# AT_SoM_Carrier_Board_V1_1.net
KiCad netlist of a schematic drawn in EAGLE
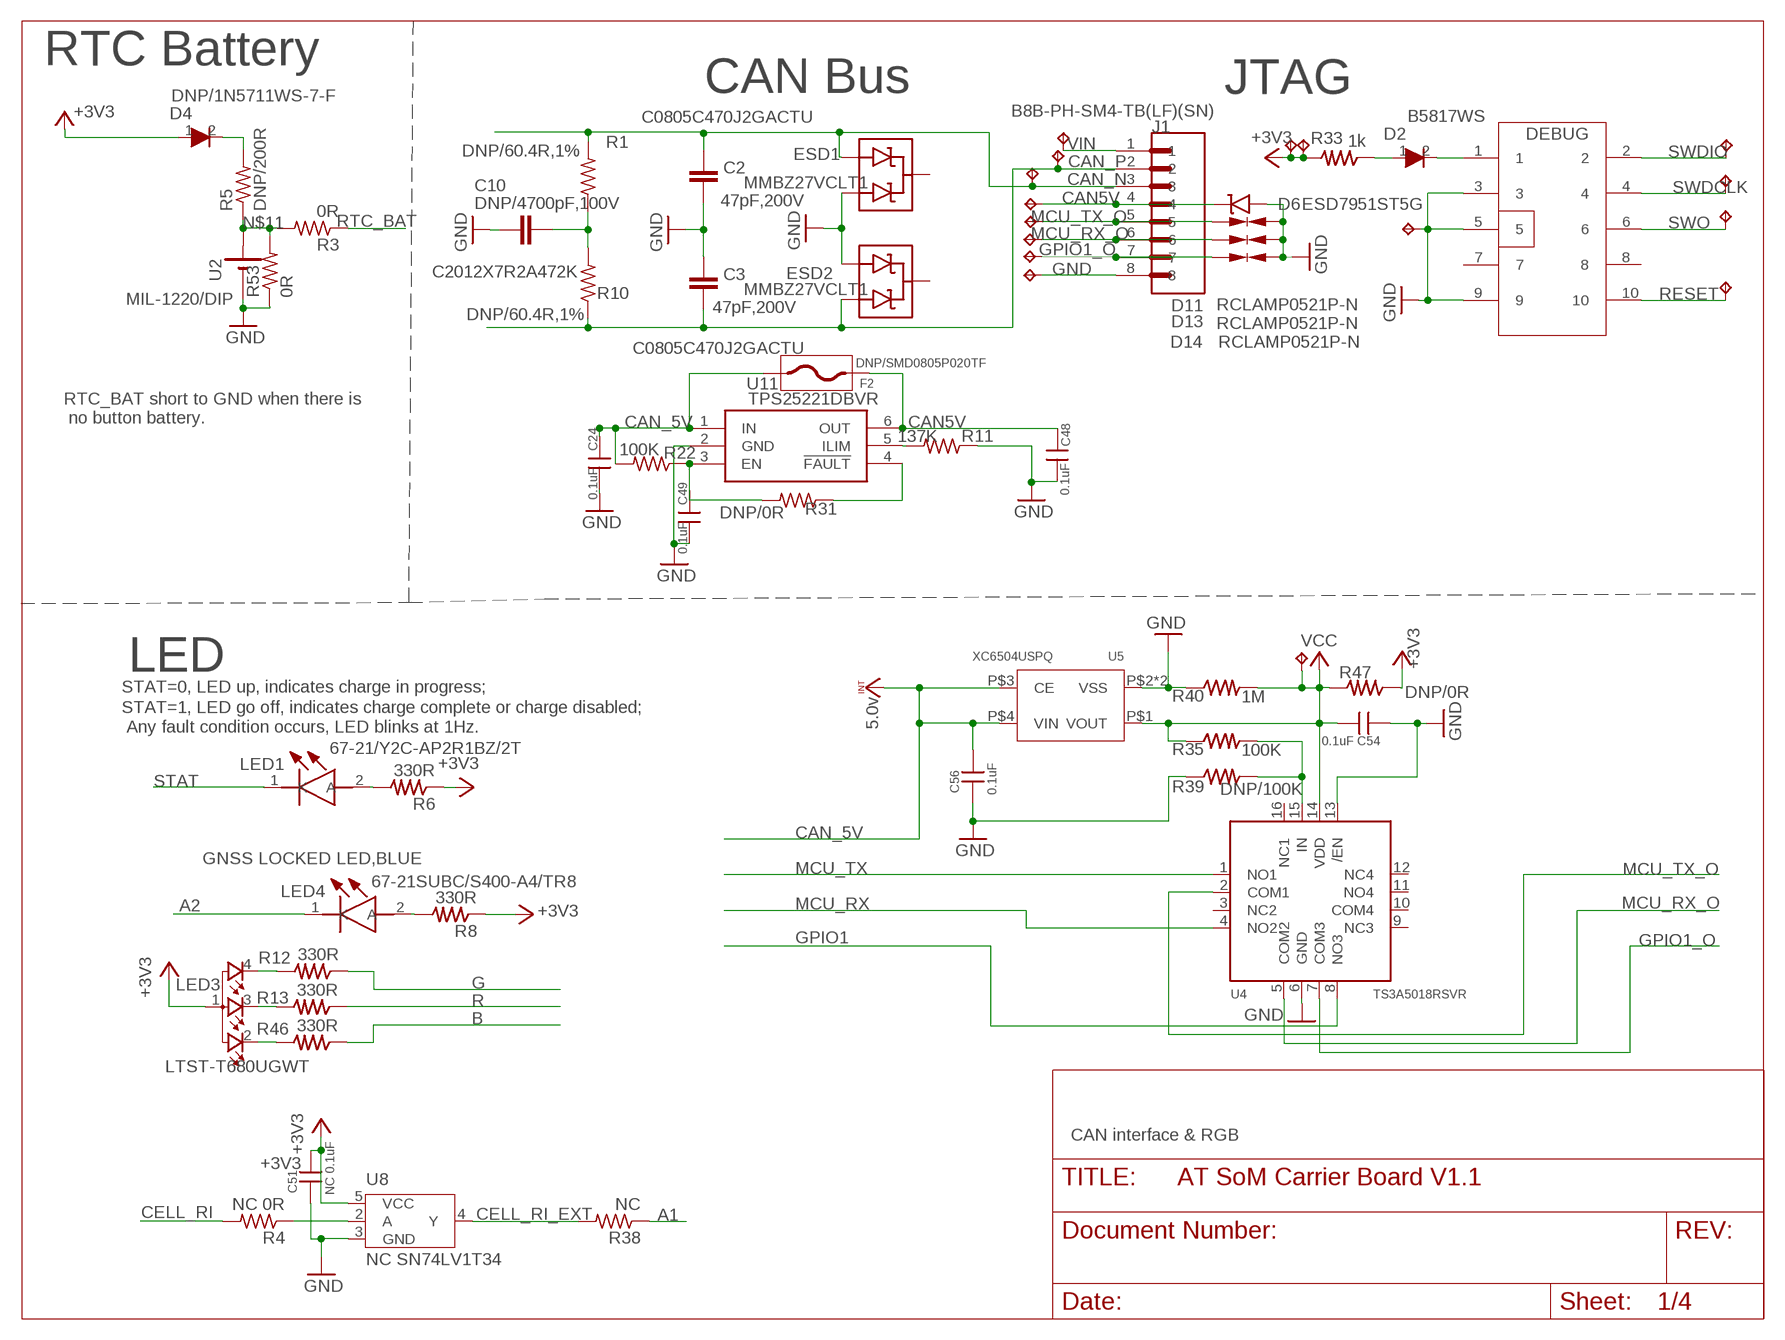
[diagram p0: schematic, sheet 1]
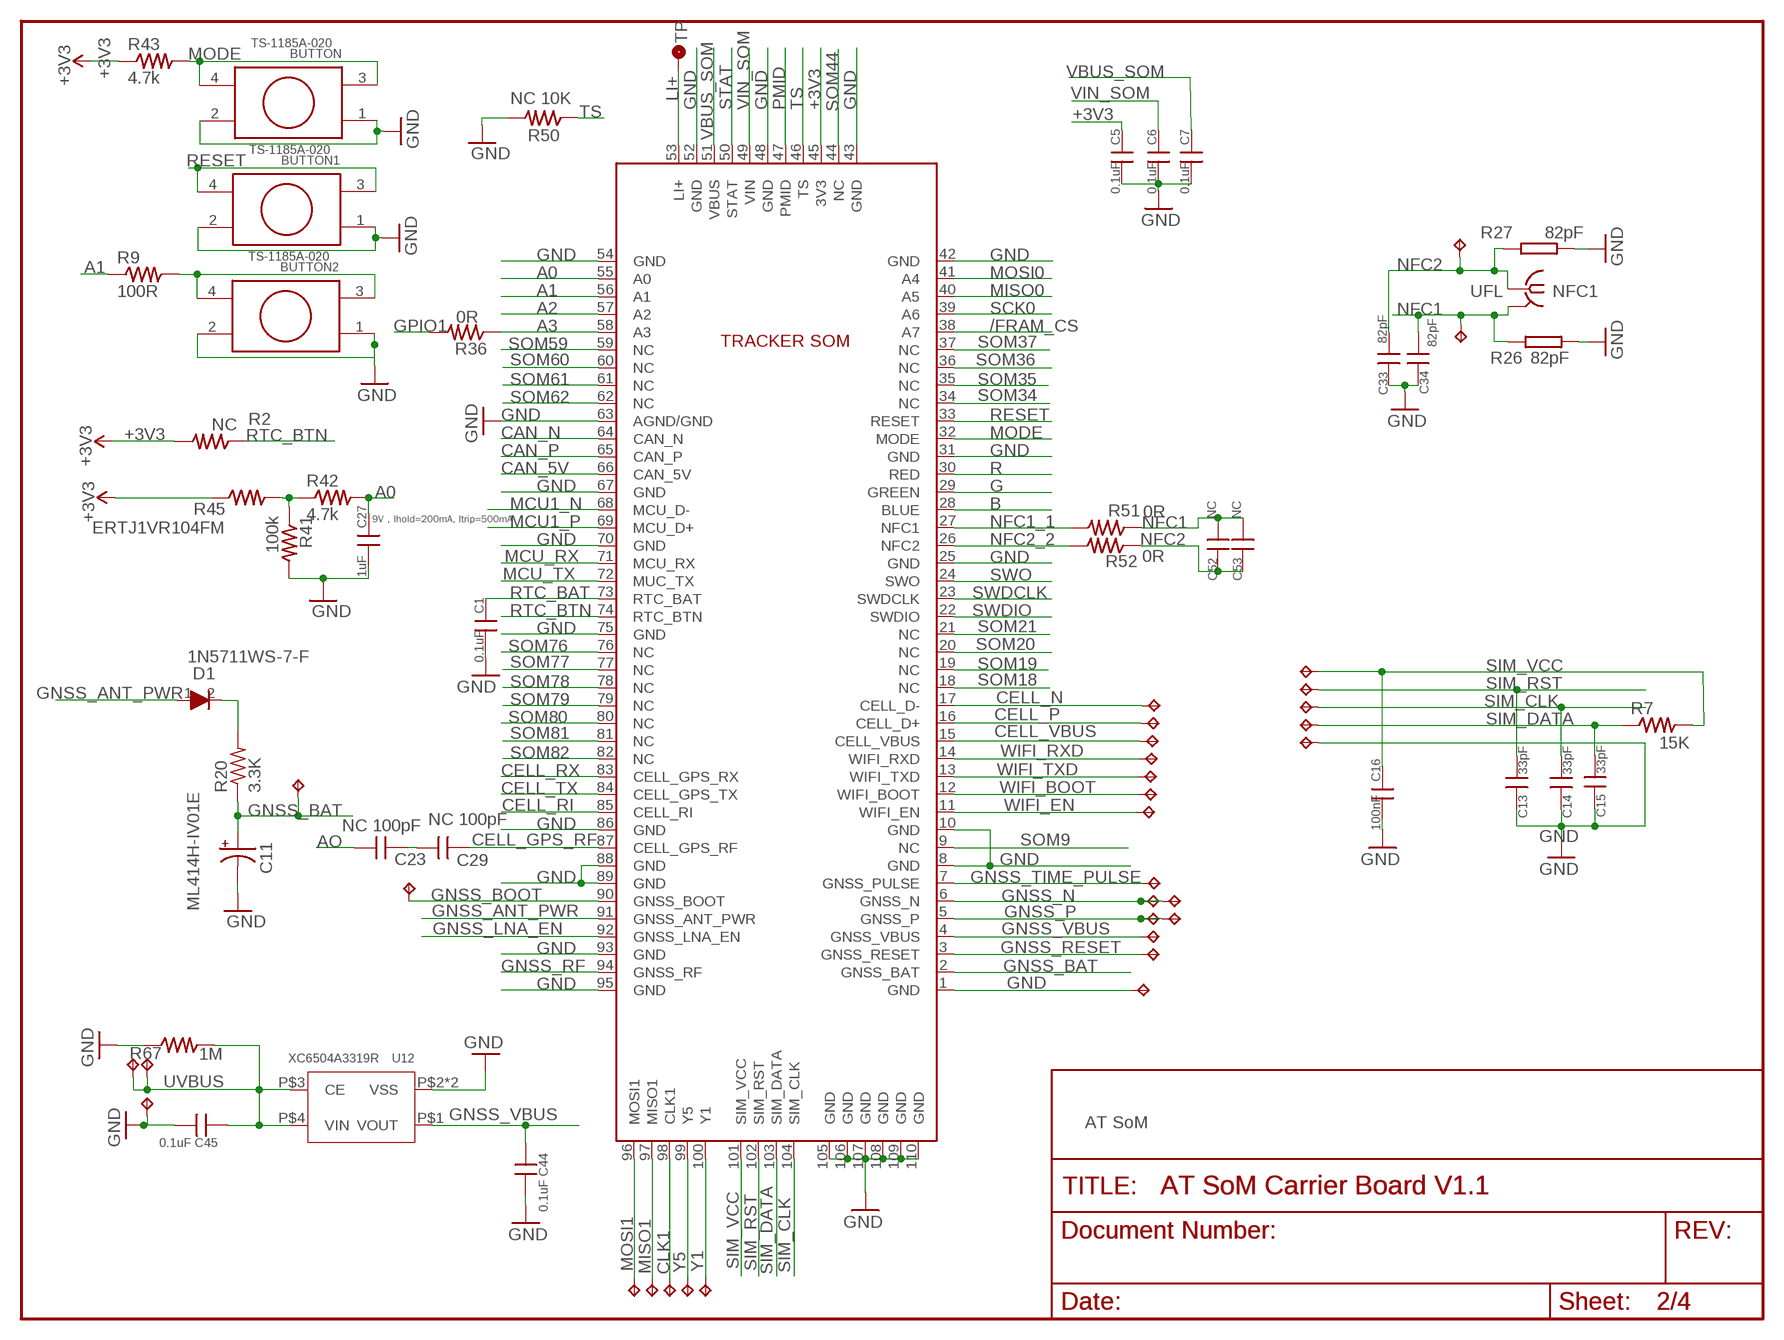
[diagram p1: schematic, sheet 2]
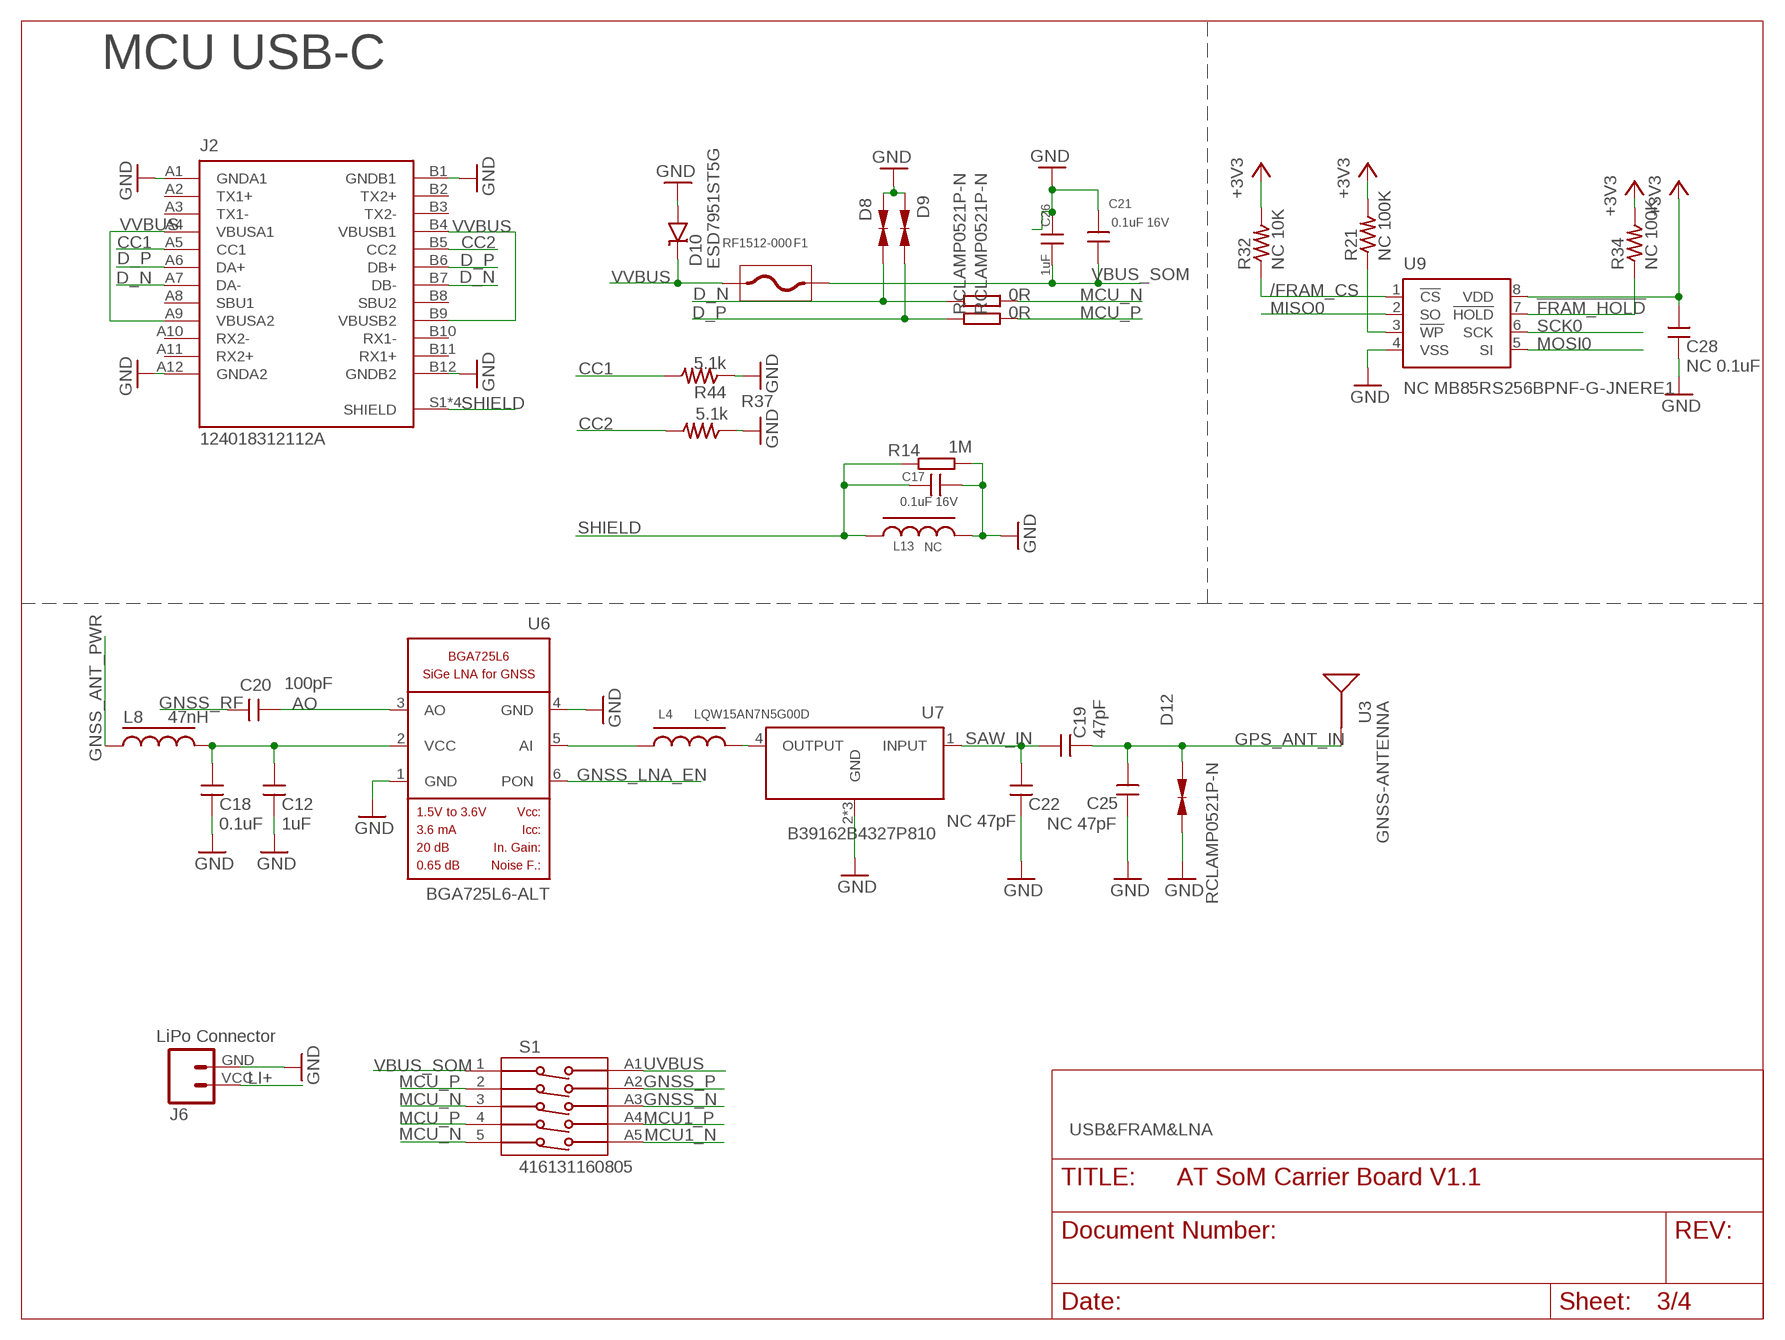
[diagram p2: schematic, sheet 3]
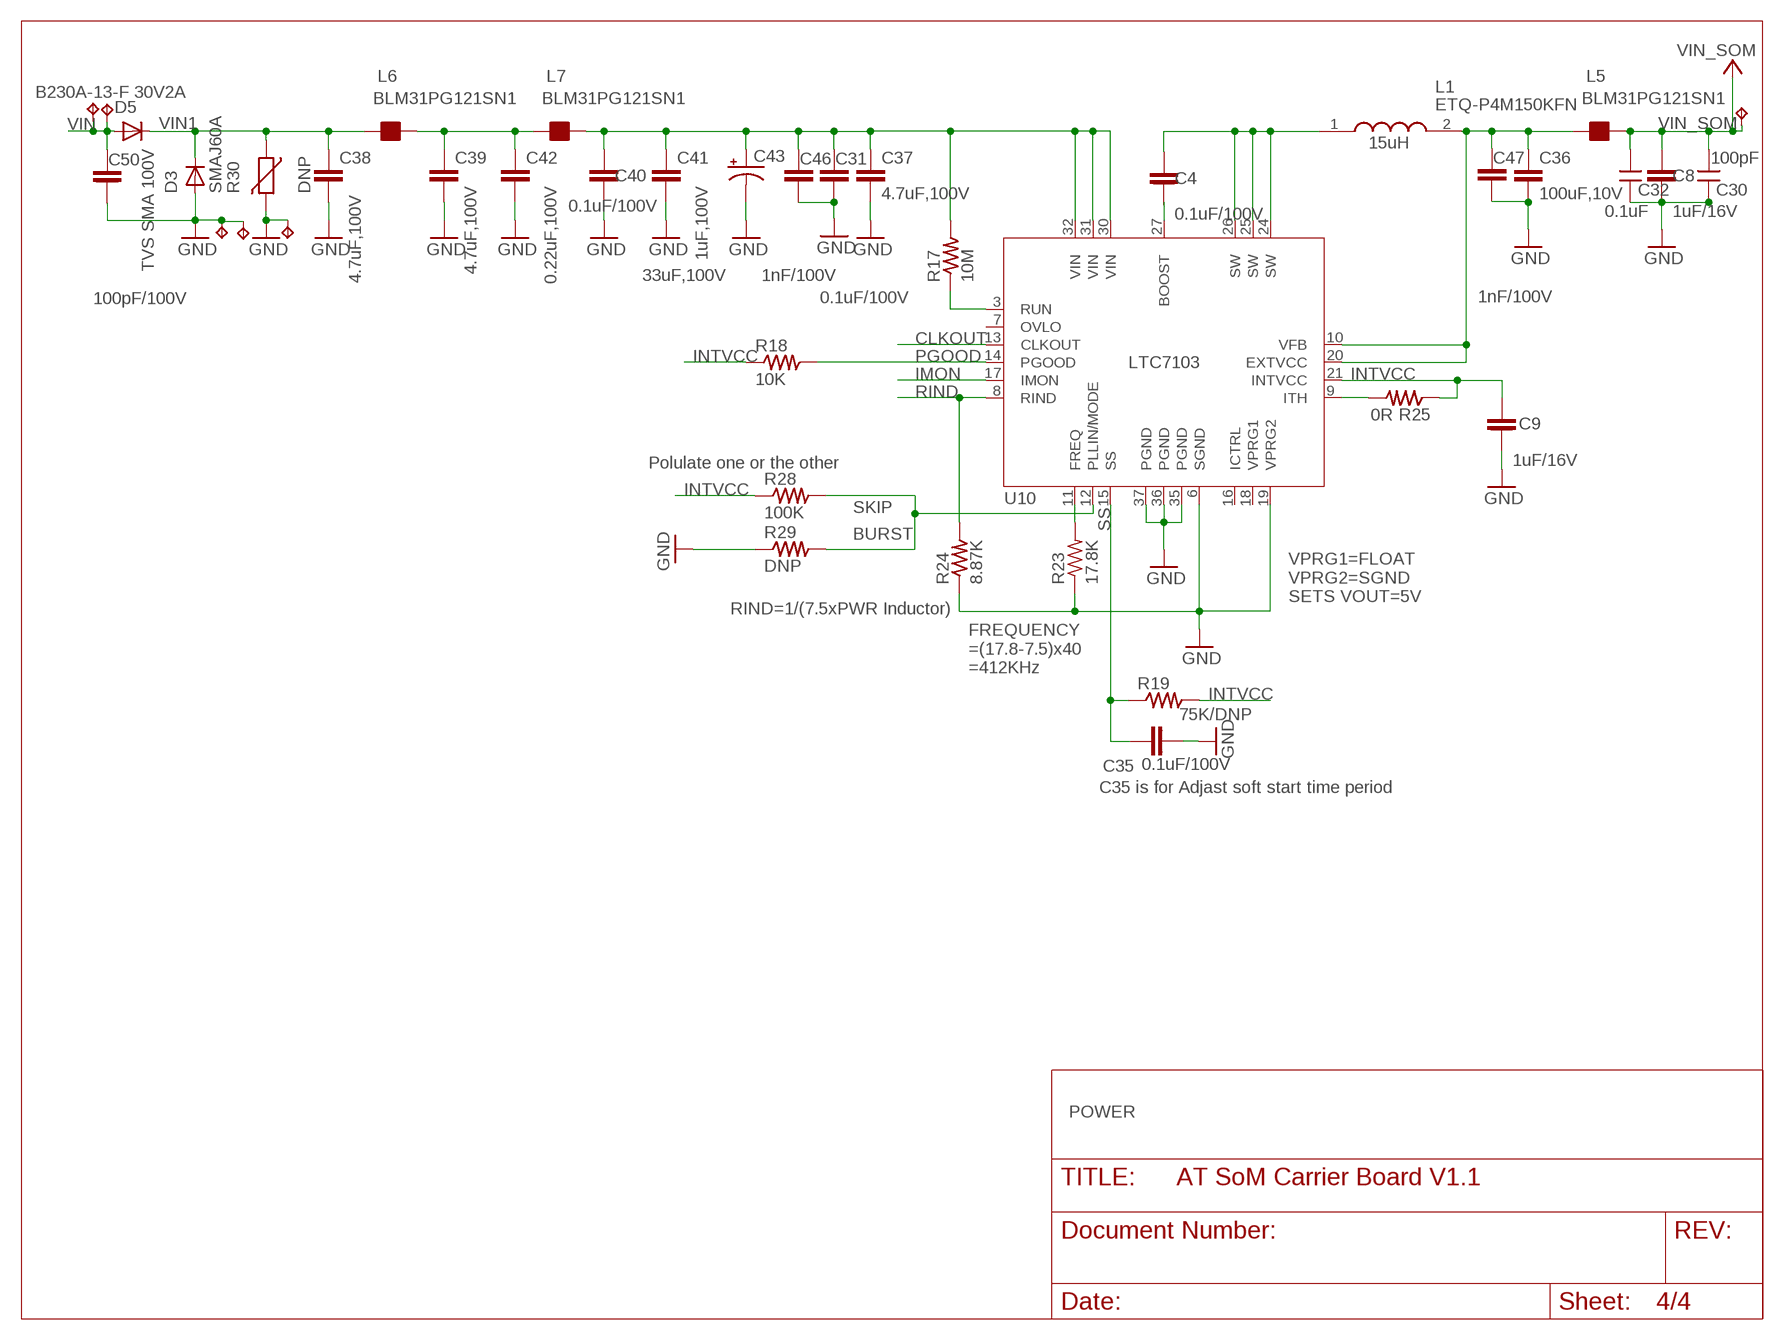
[diagram p3: schematic, sheet 4]

(export (version "E")
  (design (tool "Eeschema 10.0.6"))
  (components
    (comp (ref "BUTTON")
      (value "TS-1185A-020")
      (footprint "eagle-import:TS-1185A-020")
      (libsource (lib "eagle-import") (part "TS-1185A-020"))
    )
    (comp (ref "BUTTON1")
      (value "TS-1185A-020")
      (footprint "eagle-import:TS-1185A-020")
      (libsource (lib "eagle-import") (part "TS-1185A-020"))
    )
    (comp (ref "BUTTON2")
      (value "TS-1185A-020")
      (footprint "eagle-import:TS-1185A-020")
      (libsource (lib "eagle-import") (part "TS-1185A-020"))
    )
    (comp (ref "C1")
      (value "0.1uF")
      (footprint "eagle-import:C-0402")
      (libsource (lib "eagle-import") (part "RedBear_CAP0402"))
    )
    (comp (ref "C5")
      (value "0.1uF")
      (footprint "eagle-import:C-0402")
      (libsource (lib "eagle-import") (part "RedBear_CAP0402"))
    )
    (comp (ref "C6")
      (value "0.1uF")
      (footprint "eagle-import:C-0402")
      (libsource (lib "eagle-import") (part "RedBear_CAP0402"))
    )
    (comp (ref "C7")
      (value "0.1uF")
      (footprint "eagle-import:C-0402")
      (libsource (lib "eagle-import") (part "RedBear_CAP0402"))
    )
    (comp (ref "C11")
      (value "ML414H-IV01E")
      (footprint "eagle-import:ML414H")
      (libsource (lib "eagle-import") (part "ML414HIV01E"))
    )
    (comp (ref "C13")
      (value "33pF")
      (footprint "eagle-import:C-0402")
      (libsource (lib "eagle-import") (part "RedBear_CAP0402"))
    )
    (comp (ref "C14")
      (value "33pF")
      (footprint "eagle-import:C-0402")
      (libsource (lib "eagle-import") (part "RedBear_CAP0402"))
    )
    (comp (ref "C15")
      (value "33pF")
      (footprint "eagle-import:C-0402")
      (libsource (lib "eagle-import") (part "RedBear_CAP0402"))
    )
    (comp (ref "C16")
      (value "100nF")
      (footprint "eagle-import:C-0402")
      (libsource (lib "eagle-import") (part "RedBear_CAP0402"))
    )
    (comp (ref "C23")
      (value "NC 100pF")
      (footprint "eagle-import:C0402_P")
      (libsource (lib "eagle-import") (part "CAP_0402"))
    )
    (comp (ref "C27")
      (value "1uF")
      (footprint "eagle-import:C-0402")
      (libsource (lib "eagle-import") (part "RedBear_CAP0402"))
    )
    (comp (ref "C29")
      (value "NC 100pF")
      (footprint "eagle-import:C0402_P")
      (libsource (lib "eagle-import") (part "CAP_0402"))
    )
    (comp (ref "C33")
      (value "82pF")
      (footprint "eagle-import:C-0402")
      (libsource (lib "eagle-import") (part "RedBear_CAP0402"))
    )
    (comp (ref "C34")
      (value "82pF")
      (footprint "eagle-import:C-0402")
      (libsource (lib "eagle-import") (part "RedBear_CAP0402"))
    )
    (comp (ref "C44")
      (value "0.1uF")
      (footprint "eagle-import:C-0402")
      (libsource (lib "eagle-import") (part "RedBear_CAP0402"))
    )
    (comp (ref "C45")
      (value "0.1uF")
      (footprint "eagle-import:C-0402")
      (libsource (lib "eagle-import") (part "RedBear_CAP0402"))
    )
    (comp (ref "C52")
      (value "NC")
      (footprint "eagle-import:C-0402")
      (libsource (lib "eagle-import") (part "RedBear_CAP0402"))
    )
    (comp (ref "C53")
      (value "NC")
      (footprint "eagle-import:C-0402")
      (libsource (lib "eagle-import") (part "RedBear_CAP0402"))
    )
    (comp (ref "D1")
      (value "1N5711WS-7-F")
      (footprint "eagle-import:SOD-323")
      (libsource (lib "eagle-import") (part "DIODESOD323"))
    )
    (comp (ref "NFC1")
      (value "UFL")
      (footprint "eagle-import:IPEX-20279-001E")
      (libsource (lib "eagle-import") (part "IPEX-20279-001E"))
    )
    (comp (ref "R2")
      (value "NC")
      (footprint "eagle-import:R-0402S")
      (libsource (lib "eagle-import") (part "particle SZ_RES0402S"))
    )
    (comp (ref "R7")
      (value "15K")
      (footprint "eagle-import:R-0402S")
      (libsource (lib "eagle-import") (part "particle SZ_RES0402S"))
    )
    (comp (ref "R9")
      (value "100R")
      (footprint "eagle-import:R-0402S")
      (libsource (lib "eagle-import") (part "particle SZ_RES0402S"))
    )
    (comp (ref "R20")
      (value "3.3K")
      (footprint "eagle-import:R0603_P")
      (libsource (lib "eagle-import") (part "RES_0603"))
    )
    (comp (ref "R26")
      (value "82pF")
      (footprint "eagle-import:R-0402S")
      (libsource (lib "eagle-import") (part "RedBear_RES0402S"))
    )
    (comp (ref "R27")
      (value "82pF")
      (footprint "eagle-import:R-0402S")
      (libsource (lib "eagle-import") (part "RedBear_RES0402S"))
    )
    (comp (ref "R36")
      (value "0R")
      (footprint "eagle-import:R-0402S")
      (libsource (lib "eagle-import") (part "RES0402S"))
    )
    (comp (ref "R41")
      (value "100k")
      (footprint "eagle-import:R-0402S")
      (libsource (lib "eagle-import") (part "particle SZ_RES0402S"))
    )
    (comp (ref "R42")
      (value "4.7k")
      (footprint "eagle-import:R-0402S")
      (libsource (lib "eagle-import") (part "particle SZ_RES0402S"))
    )
    (comp (ref "R43")
      (value "4.7k")
      (footprint "eagle-import:R-0402S")
      (libsource (lib "eagle-import") (part "particle SZ_RES0402S"))
    )
    (comp (ref "R45")
      (value "ERTJ1VR104FM")
      (footprint "eagle-import:R0603")
      (libsource (lib "eagle-import") (part "RESR0603"))
    )
    (comp (ref "R50")
      (value "NC 10K")
      (footprint "eagle-import:R-0402S")
      (libsource (lib "eagle-import") (part "RES0402S"))
    )
    (comp (ref "R51")
      (value "0R")
      (footprint "eagle-import:R-0402S")
      (libsource (lib "eagle-import") (part "RES0402S"))
    )
    (comp (ref "R52")
      (value "0R")
      (footprint "eagle-import:R-0402S")
      (libsource (lib "eagle-import") (part "RES0402S"))
    )
    (comp (ref "R67")
      (value "1M")
      (footprint "eagle-import:R-0402S")
      (libsource (lib "eagle-import") (part "RES0402S"))
    )
    (comp (ref "TP1")
      (value "TPTP10R")
      (footprint "eagle-import:TP10R")
      (libsource (lib "eagle-import") (part "TPTP10R"))
    )
    (comp (ref "TP2")
      (value "TPTP10R")
      (footprint "eagle-import:TP10R")
      (libsource (lib "eagle-import") (part "TPTP10R"))
    )
    (comp (ref "TP3")
      (value "TPTP10R")
      (footprint "eagle-import:TP10R")
      (libsource (lib "eagle-import") (part "TPTP10R"))
    )
    (comp (ref "TP4")
      (value "TPTP10R")
      (footprint "eagle-import:TP10R")
      (libsource (lib "eagle-import") (part "TPTP10R"))
    )
    (comp (ref "TP5")
      (value "TPTP10R")
      (footprint "eagle-import:TP10R")
      (libsource (lib "eagle-import") (part "TPTP10R"))
    )
    (comp (ref "TP6")
      (value "TPTP10R")
      (footprint "eagle-import:TP10R")
      (libsource (lib "eagle-import") (part "TPTP10R"))
    )
    (comp (ref "TP7")
      (value "TPTP10R")
      (footprint "eagle-import:TP10R")
      (libsource (lib "eagle-import") (part "TPTP10R"))
    )
    (comp (ref "TP8")
      (value "TPTP10R")
      (footprint "eagle-import:TP10R")
      (libsource (lib "eagle-import") (part "TPTP10R"))
    )
    (comp (ref "TP9")
      (value "TPTP10R")
      (footprint "eagle-import:TP10R")
      (libsource (lib "eagle-import") (part "TPTP10R"))
    )
    (comp (ref "TP14")
      (value "TPTP10R")
      (footprint "eagle-import:TP10R")
      (libsource (lib "eagle-import") (part "TPTP10R"))
    )
    (comp (ref "TP17")
      (value "TPTP10R")
      (footprint "eagle-import:TP10R")
      (libsource (lib "eagle-import") (part "TPTP10R"))
    )
    (comp (ref "TP18")
      (value "TPTP10R")
      (footprint "eagle-import:TP10R")
      (libsource (lib "eagle-import") (part "TPTP10R"))
    )
    (comp (ref "TP19")
      (value "TPTP10R")
      (footprint "eagle-import:TP10R")
      (libsource (lib "eagle-import") (part "TPTP10R"))
    )
    (comp (ref "TP20")
      (value "TPTP10R")
      (footprint "eagle-import:TP10R")
      (libsource (lib "eagle-import") (part "TPTP10R"))
    )
    (comp (ref "TP27")
      (value "TPTP10R")
      (footprint "eagle-import:TP10R")
      (libsource (lib "eagle-import") (part "TPTP10R"))
    )
    (comp (ref "TP28")
      (value "TPTP10R")
      (footprint "eagle-import:TP10R")
      (libsource (lib "eagle-import") (part "TPTP10R"))
    )
    (comp (ref "TP29")
      (value "TPTP10R")
      (footprint "eagle-import:TP10R")
      (libsource (lib "eagle-import") (part "TPTP10R"))
    )
    (comp (ref "TP30")
      (value "TPTP10R")
      (footprint "eagle-import:TP10R")
      (libsource (lib "eagle-import") (part "TPTP10R"))
    )
    (comp (ref "TP31")
      (value "TPTP10R")
      (footprint "eagle-import:TP10R")
      (libsource (lib "eagle-import") (part "TPTP10R"))
    )
    (comp (ref "TP32")
      (value "TPTP10R")
      (footprint "eagle-import:TP10R")
      (libsource (lib "eagle-import") (part "TPTP10R"))
    )
    (comp (ref "TP33")
      (value "TPTP10R")
      (footprint "eagle-import:TP10R")
      (libsource (lib "eagle-import") (part "TPTP10R"))
    )
    (comp (ref "TP34")
      (value "TPTP10R")
      (footprint "eagle-import:TP10R")
      (libsource (lib "eagle-import") (part "TPTP10R"))
    )
    (comp (ref "TP35")
      (value "TPTP10R")
      (footprint "eagle-import:TP10R")
      (libsource (lib "eagle-import") (part "TPTP10R"))
    )
    (comp (ref "TP36")
      (value "TPTP10R")
      (footprint "eagle-import:TP10R")
      (libsource (lib "eagle-import") (part "TPTP10R"))
    )
    (comp (ref "TP37")
      (value "TPTP10R")
      (footprint "eagle-import:TP10R")
      (libsource (lib "eagle-import") (part "TPTP10R"))
    )
    (comp (ref "TP38")
      (value "TPTP10R")
      (footprint "eagle-import:TP10R")
      (libsource (lib "eagle-import") (part "TPTP10R"))
    )
    (comp (ref "TP39")
      (value "TPTP10R")
      (footprint "eagle-import:TP10R")
      (libsource (lib "eagle-import") (part "TPTP10R"))
    )
    (comp (ref "TP40")
      (value "TPTP10R")
      (footprint "eagle-import:TP10R")
      (libsource (lib "eagle-import") (part "TPTP10R"))
    )
    (comp (ref "TP41")
      (value "TPTP10R")
      (footprint "eagle-import:TP10R")
      (libsource (lib "eagle-import") (part "TPTP10R"))
    )
    (comp (ref "TP42")
      (value "TPTP10R")
      (footprint "eagle-import:TP10R")
      (libsource (lib "eagle-import") (part "TPTP10R"))
    )
    (comp (ref "U$1")
      (value "TP2")
      (footprint "eagle-import:TP70_BOT")
      (libsource (lib "eagle-import") (part "TP2"))
    )
    (comp (ref "U$9")
      (value "TPTP10R")
      (footprint "eagle-import:TP10R")
      (libsource (lib "eagle-import") (part "TPTP10R"))
    )
    (comp (ref "U$10")
      (value "TPTP10R")
      (footprint "eagle-import:TP10R")
      (libsource (lib "eagle-import") (part "TPTP10R"))
    )
    (comp (ref "U1")
      (value "TRACKERSOM_V04")
      (footprint "eagle-import:TRACKERSOM_V04")
      (libsource (lib "eagle-import") (part "TRACKERSOM_V04"))
    )
    (comp (ref "U12")
      (value "XC6504A3319R")
      (footprint "eagle-import:USPQ-4B04")
      (libsource (lib "eagle-import") (part "XC6504USPQ"))
    )
    (comp (ref "C4")
      (value "0.1uF/100V")
      (footprint "eagle-import:C-0603A")
      (libsource (lib "eagle-import") (part "CAP0603A"))
    )
    (comp (ref "C8")
      (value "1uF/16V")
      (footprint "eagle-import:C-0402")
      (libsource (lib "eagle-import") (part "CAP0402"))
    )
    (comp (ref "C9")
      (value "1uF/16V")
      (footprint "eagle-import:C-0402")
      (libsource (lib "eagle-import") (part "CAP0402"))
    )
    (comp (ref "C30")
      (value "100pF")
      (footprint "eagle-import:C0402_P")
      (libsource (lib "eagle-import") (part "CAP_0402"))
    )
    (comp (ref "C31")
      (value "0.1uF/100V")
      (footprint "eagle-import:C-0603A")
      (libsource (lib "eagle-import") (part "CAP0603A"))
    )
    (comp (ref "C32")
      (value "0.1uF")
      (footprint "eagle-import:C0402_P")
      (libsource (lib "eagle-import") (part "CAP_0402"))
    )
    (comp (ref "C35")
      (value "0.1uF/100V")
      (footprint "eagle-import:C-0603A")
      (libsource (lib "eagle-import") (part "CAP0603A"))
    )
    (comp (ref "C36")
      (value "100uF,10V")
      (footprint "eagle-import:C1210")
      (libsource (lib "eagle-import") (part "C-EUC1210"))
    )
    (comp (ref "C37")
      (value "4.7uF,100V")
      (footprint "eagle-import:C1210")
      (libsource (lib "eagle-import") (part "C-EUC1210"))
    )
    (comp (ref "C38")
      (value "4.7uF,100V")
      (footprint "eagle-import:C1210")
      (libsource (lib "eagle-import") (part "C-EUC1210"))
    )
    (comp (ref "C39")
      (value "4.7uF,100V")
      (footprint "eagle-import:C1210")
      (libsource (lib "eagle-import") (part "C-EUC1210"))
    )
    (comp (ref "C40")
      (value "0.1uF/100V")
      (footprint "eagle-import:C-0603A")
      (libsource (lib "eagle-import") (part "CAP0603A"))
    )
    (comp (ref "C41")
      (value "1uF,100V")
      (footprint "eagle-import:C0805")
      (libsource (lib "eagle-import") (part "C-EUC0805"))
    )
    (comp (ref "C42")
      (value "0.22uF,100V")
      (footprint "eagle-import:C0805")
      (libsource (lib "eagle-import") (part "C-EUC0805"))
    )
    (comp (ref "C43")
      (value "33uF,100V")
      (footprint "eagle-import:NIC_10X10.5_CAP")
      (libsource (lib "eagle-import") (part "100UF-POLAR-10X10.5-63V-20%"))
    )
    (comp (ref "C46")
      (value "1nF/100V")
      (footprint "eagle-import:C-0603A")
      (libsource (lib "eagle-import") (part "CAP0603A"))
    )
    (comp (ref "C47")
      (value "1nF/100V")
      (footprint "eagle-import:C-0603A")
      (libsource (lib "eagle-import") (part "CAP0603A"))
    )
    (comp (ref "C50")
      (value "100pF/100V")
      (footprint "eagle-import:C-0603A")
      (libsource (lib "eagle-import") (part "CAP0603A"))
    )
    (comp (ref "D3")
      (value "SMAJ60A")
      (footprint "eagle-import:SMADIODE")
      (libsource (lib "eagle-import") (part "DIODESMA"))
    )
    (comp (ref "D5")
      (value "B230A-13-F 30V2A")
      (footprint "eagle-import:SMADIODE")
      (libsource (lib "eagle-import") (part "DIODESMA"))
    )
    (comp (ref "L1")
      (value "ETQ-P4M150KFN")
      (footprint "eagle-import:ETQP4M150KFN")
      (libsource (lib "eagle-import") (part "ETQ-P4M150KFN"))
    )
    (comp (ref "L5")
      (value "BLM31PG121SN1")
      (footprint "eagle-import:L1206")
      (libsource (lib "eagle-import") (part "FB_1206"))
    )
    (comp (ref "L6")
      (value "BLM31PG121SN1")
      (footprint "eagle-import:L1206")
      (libsource (lib "eagle-import") (part "FB_1206"))
    )
    (comp (ref "L7")
      (value "BLM31PG121SN1")
      (footprint "eagle-import:L1206")
      (libsource (lib "eagle-import") (part "FB_1206"))
    )
    (comp (ref "R17")
      (value "10M")
      (footprint "eagle-import:R-0402S")
      (libsource (lib "eagle-import") (part "RES0402S"))
    )
    (comp (ref "R18")
      (value "10K")
      (footprint "eagle-import:R-0402S")
      (libsource (lib "eagle-import") (part "RES0402S"))
    )
    (comp (ref "R19")
      (value "75K/DNP")
      (footprint "eagle-import:R-0402S")
      (libsource (lib "eagle-import") (part "RES0402S"))
    )
    (comp (ref "R23")
      (value "17.8K")
      (footprint "eagle-import:R0603_P")
      (libsource (lib "eagle-import") (part "RES_0603"))
    )
    (comp (ref "R24")
      (value "8.87K")
      (footprint "eagle-import:R-0402S")
      (libsource (lib "eagle-import") (part "RES0402S"))
    )
    (comp (ref "R25")
      (value "0R")
      (footprint "eagle-import:R-0402S")
      (libsource (lib "eagle-import") (part "RES0402S"))
    )
    (comp (ref "R28")
      (value "100K")
      (footprint "eagle-import:R-0402S")
      (libsource (lib "eagle-import") (part "RES0402S"))
    )
    (comp (ref "R29")
      (value "DNP")
      (footprint "eagle-import:R-0402S")
      (libsource (lib "eagle-import") (part "RES0402S"))
    )
    (comp (ref "R30")
      (value "DNP")
      (footprint "eagle-import:R-5")
      (libsource (lib "eagle-import") (part "VARISTOR-2,5"))
    )
    (comp (ref "TP10")
      (value "TPTP10R")
      (footprint "eagle-import:TP10R")
      (libsource (lib "eagle-import") (part "TPTP10R"))
    )
    (comp (ref "TP23")
      (value "TPTP10R")
      (footprint "eagle-import:TP10R")
      (libsource (lib "eagle-import") (part "TPTP10R"))
    )
    (comp (ref "TP24")
      (value "TPTP10R")
      (footprint "eagle-import:TP10R")
      (libsource (lib "eagle-import") (part "TPTP10R"))
    )
    (comp (ref "TP25")
      (value "TPTP10R")
      (footprint "eagle-import:TP10R")
      (libsource (lib "eagle-import") (part "TPTP10R"))
    )
    (comp (ref "TP26")
      (value "TPTP10R")
      (footprint "eagle-import:TP10R")
      (libsource (lib "eagle-import") (part "TPTP10R"))
    )
    (comp (ref "TP45")
      (value "TPTP10R")
      (footprint "eagle-import:TP10R")
      (libsource (lib "eagle-import") (part "TPTP10R"))
    )
    (comp (ref "U10")
      (value "LTC7103")
      (footprint "eagle-import:UHE36(26)QFN")
      (libsource (lib "eagle-import") (part "LTC7103"))
    )
    (comp (ref "C12")
      (value "1uF")
      (footprint "eagle-import:C0402_P")
      (libsource (lib "eagle-import") (part "CAP_0402"))
    )
    (comp (ref "C17")
      (value "0.1uF 16V")
      (footprint "eagle-import:PARTICLE-SZ_C-0402")
      (libsource (lib "eagle-import") (part "PARTICLE-SZ_CAP0402"))
    )
    (comp (ref "C18")
      (value "0.1uF")
      (footprint "eagle-import:C0402_P")
      (libsource (lib "eagle-import") (part "CAP_0402"))
    )
    (comp (ref "C19")
      (value "47pF")
      (footprint "eagle-import:C0402_P")
      (libsource (lib "eagle-import") (part "CAP_0402"))
    )
    (comp (ref "C20")
      (value "100pF")
      (footprint "eagle-import:C0402_P")
      (libsource (lib "eagle-import") (part "CAP_0402"))
    )
    (comp (ref "C21")
      (value "0.1uF 16V")
      (footprint "eagle-import:C-0402")
      (libsource (lib "eagle-import") (part "RedBear_CAP0402"))
    )
    (comp (ref "C22")
      (value "NC 47pF")
      (footprint "eagle-import:C0402_P")
      (libsource (lib "eagle-import") (part "CAP_0402"))
    )
    (comp (ref "C25")
      (value "NC 47pF")
      (footprint "eagle-import:C0402_P")
      (libsource (lib "eagle-import") (part "CAP_0402"))
    )
    (comp (ref "C26")
      (value "1uF")
      (footprint "eagle-import:C-0402")
      (libsource (lib "eagle-import") (part "RedBear_CAP0402"))
    )
    (comp (ref "C28")
      (value "NC 0.1uF")
      (footprint "eagle-import:C0402_P")
      (libsource (lib "eagle-import") (part "CAP_0402"))
    )
    (comp (ref "D8")
      (value "RCLAMP0521P-N")
      (footprint "eagle-import:C0402")
      (libsource (lib "eagle-import") (part "ESD"))
    )
    (comp (ref "D9")
      (value "RCLAMP0521P-N")
      (footprint "eagle-import:C0402")
      (libsource (lib "eagle-import") (part "ESD"))
    )
    (comp (ref "D10")
      (value "ESD7951ST5G")
      (footprint "eagle-import:0402-TVS-UNIDIR")
      (libsource (lib "eagle-import") (part "ESD-TVS-UNIDIR"))
    )
    (comp (ref "D12")
      (value "RCLAMP0521P-N")
      (footprint "eagle-import:C0402")
      (libsource (lib "eagle-import") (part "ESD"))
    )
    (comp (ref "F1")
      (value "RF1512-000")
      (footprint "eagle-import:R1206")
      (libsource (lib "eagle-import") (part "FUSEF1206"))
    )
    (comp (ref "J2")
      (value "124018312112A")
      (footprint "eagle-import:AMPHENOL_124018312112A")
      (fields (field (name "MF") "Amphenol ICC"))
      (libsource (lib "eagle-import") (part "124018312112A"))
    )
    (comp (ref "J6")
      (value "M024UCON-15767")
      (footprint "eagle-import:JST-2-SMD-VERT")
      (libsource (lib "eagle-import") (part "M024UCON-15767"))
    )
    (comp (ref "L4")
      (value "LQW15AN7N5G00D")
      (footprint "eagle-import:R-0402S")
      (libsource (lib "eagle-import") (part "L0402"))
    )
    (comp (ref "L8")
      (value "47nH")
      (footprint "eagle-import:R-0402S")
      (libsource (lib "eagle-import") (part "particle SZ_L0402"))
    )
    (comp (ref "L13")
      (value "NC")
      (footprint "eagle-import:R-0603A")
      (libsource (lib "eagle-import") (part "L"))
    )
    (comp (ref "R14")
      (value "1M")
      (footprint "eagle-import:REDBEAR_R0603")
      (libsource (lib "eagle-import") (part "REDBEAR_RESR0603"))
    )
    (comp (ref "R15")
      (value "0R")
      (footprint "eagle-import:R-0402S")
      (libsource (lib "eagle-import") (part "RedBear_RES0402S"))
    )
    (comp (ref "R16")
      (value "0R")
      (footprint "eagle-import:R-0402S")
      (libsource (lib "eagle-import") (part "RedBear_RES0402S"))
    )
    (comp (ref "R21")
      (value "NC 100K")
      (footprint "eagle-import:R-0402S")
      (libsource (lib "eagle-import") (part "RES0402S"))
    )
    (comp (ref "R32")
      (value "NC 10K")
      (footprint "eagle-import:R-0402S")
      (libsource (lib "eagle-import") (part "RES0402S"))
    )
    (comp (ref "R34")
      (value "NC 100K")
      (footprint "eagle-import:R-0402S")
      (libsource (lib "eagle-import") (part "RES0402S"))
    )
    (comp (ref "R37")
      (value "5.1k")
      (footprint "eagle-import:R-0402S")
      (libsource (lib "eagle-import") (part "RES0402S"))
    )
    (comp (ref "R44")
      (value "5.1k")
      (footprint "eagle-import:R-0402S")
      (libsource (lib "eagle-import") (part "RES0402S"))
    )
    (comp (ref "S1")
      (value "416131160805")
      (footprint "eagle-import:416131160805")
      (fields (field (name "MF") "Wurth Electronics"))
      (libsource (lib "eagle-import") (part "416131160805"))
    )
    (comp (ref "U3")
      (value "GNSS-ANTENNA")
      (footprint "eagle-import:PA035AZ0004")
      (libsource (lib "eagle-import") (part "GNSS-ANTENNA"))
    )
    (comp (ref "U6")
      (value "BGA725L6-ALT")
      (footprint "eagle-import:LNA-TSLP-6-2-ALT")
      (libsource (lib "eagle-import") (part "BGA725L6-ALT"))
    )
    (comp (ref "U7")
      (value "B39162B4327P810")
      (footprint "eagle-import:QCS5I")
      (libsource (lib "eagle-import") (part "FILTERS"))
    )
    (comp (ref "U9")
      (value "NC MB85RS256BPNF-G-JNERE1")
      (footprint "eagle-import:SO08")
      (libsource (lib "eagle-import") (part "MB85RS1MT"))
    )
    (comp (ref "C2")
      (value "47pF,200V")
      (footprint "eagle-import:C0805")
      (fields (field (name "PART_NUMBER") "C0805C470J2GACTU"))
      (libsource (lib "eagle-import") (part "C-EUC0805"))
    )
    (comp (ref "C3")
      (value "47pF,200V")
      (footprint "eagle-import:C0805")
      (fields (field (name "PART_NUMBER") "C0805C470J2GACTU"))
      (libsource (lib "eagle-import") (part "C-EUC0805"))
    )
    (comp (ref "C10")
      (value "DNP/4700pF,100V")
      (footprint "eagle-import:C0805")
      (fields (field (name "PART_NUMBER") "C2012X7R2A472K"))
      (libsource (lib "eagle-import") (part "C-EUC0805"))
    )
    (comp (ref "C24")
      (value "0.1uF")
      (footprint "eagle-import:C-0402")
      (libsource (lib "eagle-import") (part "RedBear_CAP0402"))
    )
    (comp (ref "C48")
      (value "0.1uF")
      (footprint "eagle-import:C-0402")
      (libsource (lib "eagle-import") (part "RedBear_CAP0402"))
    )
    (comp (ref "C49")
      (value "0.1uF")
      (footprint "eagle-import:C-0402")
      (libsource (lib "eagle-import") (part "RedBear_CAP0402"))
    )
    (comp (ref "C51")
      (value "NC 0.1uF")
      (footprint "eagle-import:C-0402")
      (libsource (lib "eagle-import") (part "RedBear_CAP0402"))
    )
    (comp (ref "C54")
      (value "0.1uF")
      (footprint "eagle-import:C-0402")
      (libsource (lib "eagle-import") (part "RedBear_CAP0402"))
    )
    (comp (ref "C56")
      (value "0.1uF")
      (footprint "eagle-import:C-0402")
      (libsource (lib "eagle-import") (part "RedBear_CAP0402"))
    )
    (comp (ref "D2")
      (value "B5817WS")
      (footprint "eagle-import:SOD-323")
      (libsource (lib "eagle-import") (part "DIODESOD323"))
    )
    (comp (ref "D4")
      (value "DNP/1N5711WS-7-F")
      (footprint "eagle-import:SOD-323")
      (libsource (lib "eagle-import") (part "DIODESOD323"))
    )
    (comp (ref "D6")
      (value "ESD7951ST5G")
      (footprint "eagle-import:0402-TVS-UNIDIR")
      (libsource (lib "eagle-import") (part "ESD-TVS-UNIDIR"))
    )
    (comp (ref "D11")
      (value "RCLAMP0521P-N")
      (footprint "eagle-import:C0402")
      (libsource (lib "eagle-import") (part "ESD"))
    )
    (comp (ref "D13")
      (value "RCLAMP0521P-N")
      (footprint "eagle-import:C0402")
      (libsource (lib "eagle-import") (part "ESD"))
    )
    (comp (ref "D14")
      (value "RCLAMP0521P-N")
      (footprint "eagle-import:C0402")
      (libsource (lib "eagle-import") (part "ESD"))
    )
    (comp (ref "DEBUG")
      (value "CON5X2")
      (footprint "eagle-import:CON5X2_1.27")
      (libsource (lib "eagle-import") (part "CON5X2"))
    )
    (comp (ref "ESD1")
      (value "MMBZ27VCLT1")
      (footprint "eagle-import:SOT23-3")
      (libsource (lib "eagle-import") (part "MMBZ27VCLT1"))
    )
    (comp (ref "ESD2")
      (value "MMBZ27VCLT1")
      (footprint "eagle-import:SOT23-3")
      (libsource (lib "eagle-import") (part "MMBZ27VCLT1"))
    )
    (comp (ref "F2")
      (value "DNP/SMD0805P020TF")
      (footprint "eagle-import:F0805")
      (libsource (lib "eagle-import") (part "FUSE"))
    )
    (comp (ref "J1")
      (value "B8B-PH-SM4-TB(LF)(SN)")
      (footprint "eagle-import:JST_B8B-PH-SM4-TB(LF)(SN)")
      (libsource (lib "eagle-import") (part "B8B-PH-SM4-TB(LF)(SN)"))
    )
    (comp (ref "LED1")
      (value "67-21/Y2C-AP2R1BZ/2T")
      (footprint "eagle-import:LEDM3528X210N")
      (fields
        (field (name "MANUFACTURER_PART_NUMBER") "150141GS73113")
        (field (name "MOUSER_PART_NUMBER") "710-150141GS73113")
        (field (name "RS_PART_NUMBER") "1847238P")
      )
      (libsource (lib "eagle-import") (part "150141GS73113"))
    )
    (comp (ref "LED3")
      (value "LTST-T680UGWT")
      (footprint "eagle-import:150141M173100")
      (libsource (lib "eagle-import") (part "150141M173100"))
    )
    (comp (ref "LED4")
      (value "67-21SUBC/S400-A4/TR8")
      (footprint "eagle-import:LEDM3528X210N")
      (fields
        (field (name "MANUFACTURER_PART_NUMBER") "150141GS73113")
        (field (name "MOUSER_PART_NUMBER") "710-150141GS73113")
        (field (name "RS_PART_NUMBER") "1847238P")
      )
      (libsource (lib "eagle-import") (part "150141GS73113"))
    )
    (comp (ref "R1")
      (value "DNP/60.4R,1%")
      (footprint "eagle-import:R1206")
      (libsource (lib "eagle-import") (part "R-US_R1206"))
    )
    (comp (ref "R3")
      (value "0R")
      (footprint "eagle-import:R0402_B")
      (libsource (lib "eagle-import") (part "R-US_"))
    )
    (comp (ref "R4")
      (value "NC 0R")
      (footprint "eagle-import:R0402_B")
      (libsource (lib "eagle-import") (part "R-US_"))
    )
    (comp (ref "R5")
      (value "DNP/200R")
      (footprint "eagle-import:R0402_B")
      (libsource (lib "eagle-import") (part "R-US_"))
    )
    (comp (ref "R6")
      (value "330R")
      (footprint "eagle-import:R-0402S")
      (libsource (lib "eagle-import") (part "particle SZ_RES0402S"))
    )
    (comp (ref "R8")
      (value "330R")
      (footprint "eagle-import:R-0402S")
      (libsource (lib "eagle-import") (part "particle SZ_RES0402S"))
    )
    (comp (ref "R10")
      (value "DNP/60.4R,1%")
      (footprint "eagle-import:R1206")
      (libsource (lib "eagle-import") (part "R-US_R1206"))
    )
    (comp (ref "R11")
      (value "137K")
      (footprint "eagle-import:R0402_B")
      (libsource (lib "eagle-import") (part "R-US_"))
    )
    (comp (ref "R12")
      (value "330R")
      (footprint "eagle-import:R-0402S")
      (libsource (lib "eagle-import") (part "particle SZ_RES0402S"))
    )
    (comp (ref "R13")
      (value "330R")
      (footprint "eagle-import:R-0402S")
      (libsource (lib "eagle-import") (part "particle SZ_RES0402S"))
    )
    (comp (ref "R22")
      (value "100K")
      (footprint "eagle-import:R0402_B")
      (libsource (lib "eagle-import") (part "R-US_"))
    )
    (comp (ref "R31")
      (value "DNP/0R")
      (footprint "eagle-import:R0402_B")
      (libsource (lib "eagle-import") (part "R-US_"))
    )
    (comp (ref "R33")
      (value "1k")
      (footprint "eagle-import:R-0402S")
      (libsource (lib "eagle-import") (part "particle SZ_RES0402S"))
    )
    (comp (ref "R35")
      (value "100K")
      (footprint "eagle-import:R-0402S")
      (libsource (lib "eagle-import") (part "RES0402S"))
    )
    (comp (ref "R38")
      (value "NC")
      (footprint "eagle-import:R0402_B")
      (libsource (lib "eagle-import") (part "R-US_"))
    )
    (comp (ref "R39")
      (value "DNP/100K")
      (footprint "eagle-import:R-0402S")
      (libsource (lib "eagle-import") (part "RES0402S"))
    )
    (comp (ref "R40")
      (value "1M")
      (footprint "eagle-import:R-0402S")
      (libsource (lib "eagle-import") (part "RES0402S"))
    )
    (comp (ref "R46")
      (value "330R")
      (footprint "eagle-import:R-0402S")
      (libsource (lib "eagle-import") (part "particle SZ_RES0402S"))
    )
    (comp (ref "R47")
      (value "DNP/0R")
      (footprint "eagle-import:R-0402S")
      (libsource (lib "eagle-import") (part "particle SZ_RES0402S"))
    )
    (comp (ref "R53")
      (value "0R")
      (footprint "eagle-import:R0402_B")
      (libsource (lib "eagle-import") (part "R-US_"))
    )
    (comp (ref "TP11")
      (value "TPTP10R")
      (footprint "eagle-import:TP10R")
      (libsource (lib "eagle-import") (part "TPTP10R"))
    )
    (comp (ref "TP12")
      (value "TPTP10R")
      (footprint "eagle-import:TP10R")
      (libsource (lib "eagle-import") (part "TPTP10R"))
    )
    (comp (ref "TP13")
      (value "TPTP10R")
      (footprint "eagle-import:TP10R")
      (libsource (lib "eagle-import") (part "TPTP10R"))
    )
    (comp (ref "TP15")
      (value "TPTP10R")
      (footprint "eagle-import:TP10R")
      (libsource (lib "eagle-import") (part "TPTP10R"))
    )
    (comp (ref "TP16")
      (value "TPTP10R")
      (footprint "eagle-import:TP10R")
      (libsource (lib "eagle-import") (part "TPTP10R"))
    )
    (comp (ref "TP21")
      (value "TPTP10R")
      (footprint "eagle-import:TP10R")
      (libsource (lib "eagle-import") (part "TPTP10R"))
    )
    (comp (ref "TP22")
      (value "TPTP10R")
      (footprint "eagle-import:TP10R")
      (libsource (lib "eagle-import") (part "TPTP10R"))
    )
    (comp (ref "TP43")
      (value "TPTP10R")
      (footprint "eagle-import:TP10R")
      (libsource (lib "eagle-import") (part "TPTP10R"))
    )
    (comp (ref "TP44")
      (value "TPTP10R")
      (footprint "eagle-import:TP10R")
      (libsource (lib "eagle-import") (part "TPTP10R"))
    )
    (comp (ref "TP46")
      (value "TPTP10R")
      (footprint "eagle-import:TP10R")
      (libsource (lib "eagle-import") (part "TPTP10R"))
    )
    (comp (ref "TP47")
      (value "TPTP10R")
      (footprint "eagle-import:TP10R")
      (libsource (lib "eagle-import") (part "TPTP10R"))
    )
    (comp (ref "TP48")
      (value "TPTP10R")
      (footprint "eagle-import:TP10R")
      (libsource (lib "eagle-import") (part "TPTP10R"))
    )
    (comp (ref "TP49")
      (value "TPTP10R")
      (footprint "eagle-import:TP10R")
      (libsource (lib "eagle-import") (part "TPTP10R"))
    )
    (comp (ref "TP50")
      (value "TPTP10R")
      (footprint "eagle-import:TP10R")
      (libsource (lib "eagle-import") (part "TPTP10R"))
    )
    (comp (ref "TP51")
      (value "TPTP10R")
      (footprint "eagle-import:TP10R")
      (libsource (lib "eagle-import") (part "TPTP10R"))
    )
    (comp (ref "TP52")
      (value "TPTP10R")
      (footprint "eagle-import:TP10R")
      (libsource (lib "eagle-import") (part "TPTP10R"))
    )
    (comp (ref "U2")
      (value "MIL-1220/DIP")
      (footprint "eagle-import:BAT_ML-1220_DIP")
      (libsource (lib "eagle-import") (part "ML-1220/F1ANBAT_MIL-1220/DIP"))
    )
    (comp (ref "U4")
      (value "TS3A5018RSVR")
      (footprint "eagle-import:UQFN-16")
      (libsource (lib "eagle-import") (part "TS3A5018RSVR"))
    )
    (comp (ref "U5")
      (value "XC6504USPQ")
      (footprint "eagle-import:USPQ-4B04")
      (libsource (lib "eagle-import") (part "XC6504USPQ"))
    )
    (comp (ref "U8")
      (value "NC SN74LV1T34")
      (footprint "eagle-import:SC70-5")
      (libsource (lib "eagle-import") (part "SN74LV1T34"))
    )
    (comp (ref "U11")
      (value "TPS25221DBVR")
      (footprint "eagle-import:SOT95P280X145-6N")
      (fields (field (name "MOUSER_PART_NUMBER") "595-TPS25221DBVR"))
      (libsource (lib "eagle-import") (part "TPS25221DBVR"))
    )
  )
  (nets
    (net (code "1") (name "+3V3") (class "Default")
      (node (ref "C28") (pin "1") (pinfunction "1_1") (pintype "bidirectional"))
      (node (ref "C5") (pin "1") (pinfunction "1_1") (pintype "bidirectional"))
      (node (ref "C51") (pin "1") (pinfunction "1_1") (pintype "bidirectional"))
      (node (ref "D4") (pin "1") (pinfunction "P$1_1") (pintype "bidirectional"))
      (node (ref "LED3") (pin "1") (pinfunction "1_1") (pintype "passive"))
      (node (ref "R2") (pin "2") (pinfunction "2_2") (pintype "bidirectional"))
      (node (ref "R21") (pin "2") (pinfunction "2_2") (pintype "bidirectional"))
      (node (ref "R32") (pin "2") (pinfunction "2_2") (pintype "bidirectional"))
      (node (ref "R33") (pin "2") (pinfunction "2_2") (pintype "bidirectional"))
      (node (ref "R34") (pin "2") (pinfunction "2_2") (pintype "bidirectional"))
      (node (ref "R43") (pin "1") (pinfunction "1_1") (pintype "bidirectional"))
      (node (ref "R45") (pin "1") (pinfunction "1_1") (pintype "bidirectional"))
      (node (ref "R47") (pin "1") (pinfunction "1_1") (pintype "bidirectional"))
      (node (ref "R6") (pin "1") (pinfunction "1_1") (pintype "bidirectional"))
      (node (ref "R8") (pin "1") (pinfunction "1_1") (pintype "bidirectional"))
      (node (ref "TP16") (pin "TP") (pinfunction "TP_TP") (pintype "input"))
      (node (ref "TP21") (pin "TP") (pinfunction "TP_TP") (pintype "input"))
      (node (ref "U1") (pin "45") (pinfunction "3V3_45") (pintype "bidirectional"))
      (node (ref "U8") (pin "5") (pinfunction "VCC_5") (pintype "power_in"))
      (node (ref "U9") (pin "8") (pinfunction "VDD_8") (pintype "power_in"))
    )
    (net (code "2") (name "A0") (class "Default")
      (node (ref "C27") (pin "1") (pinfunction "1_1") (pintype "bidirectional"))
      (node (ref "R42") (pin "2") (pinfunction "2_2") (pintype "bidirectional"))
      (node (ref "U1") (pin "55") (pinfunction "A0_55") (pintype "bidirectional"))
    )
    (net (code "3") (name "A1") (class "Default")
      (node (ref "R38") (pin "1") (pinfunction "1_1") (pintype "passive"))
      (node (ref "R9") (pin "1") (pinfunction "1_1") (pintype "bidirectional"))
      (node (ref "U1") (pin "56") (pinfunction "A1_56") (pintype "bidirectional"))
    )
    (net (code "4") (name "A2") (class "Default")
      (node (ref "LED4") (pin "1") (pinfunction "K_1") (pintype "bidirectional"))
      (node (ref "U1") (pin "57") (pinfunction "A2_57") (pintype "bidirectional"))
    )
    (net (code "5") (name "A3") (class "Default")
      (node (ref "R36") (pin "1") (pinfunction "1_1") (pintype "bidirectional"))
      (node (ref "U1") (pin "58") (pinfunction "A3_58") (pintype "bidirectional"))
    )
    (net (code "6") (name "AO") (class "Default")
      (node (ref "C20") (pin "2") (pinfunction "2_2") (pintype "bidirectional"))
      (node (ref "C23") (pin "1") (pinfunction "1_1") (pintype "bidirectional"))
      (node (ref "U6") (pin "3") (pinfunction "AO_3") (pintype "output"))
    )
    (net (code "7") (name "B") (class "Default")
      (node (ref "R46") (pin "1") (pinfunction "1_1") (pintype "bidirectional"))
      (node (ref "U1") (pin "28") (pinfunction "BLUE_28") (pintype "bidirectional"))
    )
    (net (code "8") (name "CAN5V") (class "Default")
      (node (ref "C48") (pin "1") (pinfunction "1_1") (pintype "bidirectional"))
      (node (ref "D6") (pin "1") (pinfunction "1_1") (pintype "passive"))
      (node (ref "F2") (pin "P$1") (pinfunction "1_P$1") (pintype "bidirectional"))
      (node (ref "J1") (pin "4") (pinfunction "4_4") (pintype "passive"))
      (node (ref "TP48") (pin "TP") (pinfunction "TP_TP") (pintype "input"))
      (node (ref "U11") (pin "6") (pinfunction "OUT_6") (pintype "bidirectional"))
    )
    (net (code "9") (name "CAN_5V") (class "Default")
      (node (ref "C24") (pin "1") (pinfunction "1_1") (pintype "bidirectional"))
      (node (ref "C56") (pin "1") (pinfunction "1_1") (pintype "bidirectional"))
      (node (ref "F2") (pin "P$2") (pinfunction "2_P$2") (pintype "bidirectional"))
      (node (ref "R22") (pin "2") (pinfunction "2_2") (pintype "passive"))
      (node (ref "U1") (pin "66") (pinfunction "CAN_5V_66") (pintype "bidirectional"))
      (node (ref "U11") (pin "1") (pinfunction "IN_1") (pintype "bidirectional"))
      (node (ref "U5") (pin "P$3") (pinfunction "CE_P$3") (pintype "bidirectional"))
      (node (ref "U5") (pin "P$4") (pinfunction "VIN_P$4") (pintype "bidirectional"))
    )
    (net (code "10") (name "CAN_N") (class "Default")
      (node (ref "C2") (pin "1") (pinfunction "1_1") (pintype "passive"))
      (node (ref "ESD1") (pin "2") (pinfunction "A2_2") (pintype "passive"))
      (node (ref "J1") (pin "3") (pinfunction "3_3") (pintype "passive"))
      (node (ref "R1") (pin "2") (pinfunction "2_2") (pintype "passive"))
      (node (ref "TP47") (pin "TP") (pinfunction "TP_TP") (pintype "input"))
      (node (ref "U1") (pin "64") (pinfunction "CAN_N_64") (pintype "bidirectional"))
    )
    (net (code "11") (name "CAN_P") (class "Default")
      (node (ref "C3") (pin "2") (pinfunction "2_2") (pintype "passive"))
      (node (ref "ESD2") (pin "1") (pinfunction "A1_1") (pintype "passive"))
      (node (ref "J1") (pin "2") (pinfunction "2_2") (pintype "passive"))
      (node (ref "R10") (pin "1") (pinfunction "1_1") (pintype "passive"))
      (node (ref "TP46") (pin "TP") (pinfunction "TP_TP") (pintype "input"))
      (node (ref "U1") (pin "65") (pinfunction "CAN_P_65") (pintype "bidirectional"))
    )
    (net (code "12") (name "CC1") (class "Default")
      (node (ref "J2") (pin "A5") (pinfunction "CC1_A5") (pintype "bidirectional"))
      (node (ref "R44") (pin "2") (pinfunction "2_2") (pintype "bidirectional"))
    )
    (net (code "13") (name "CC2") (class "Default")
      (node (ref "J2") (pin "B5") (pinfunction "CC2_B5") (pintype "bidirectional"))
      (node (ref "R37") (pin "2") (pinfunction "2_2") (pintype "bidirectional"))
    )
    (net (code "14") (name "CELL_GPS_RF") (class "Default")
      (node (ref "C29") (pin "2") (pinfunction "2_2") (pintype "bidirectional"))
      (node (ref "U1") (pin "87") (pinfunction "CELL_GPS_RF_87") (pintype "bidirectional"))
    )
    (net (code "15") (name "CELL_N") (class "Default")
      (node (ref "TP38") (pin "TP") (pinfunction "TP_TP") (pintype "input"))
      (node (ref "U1") (pin "17") (pinfunction "CELL_D-_17") (pintype "bidirectional"))
    )
    (net (code "16") (name "CELL_P") (class "Default")
      (node (ref "TP36") (pin "TP") (pinfunction "TP_TP") (pintype "input"))
      (node (ref "U1") (pin "16") (pinfunction "CELL_D+_16") (pintype "bidirectional"))
    )
    (net (code "17") (name "CELL_RI") (class "Default")
      (node (ref "R4") (pin "2") (pinfunction "2_2") (pintype "passive"))
      (node (ref "U1") (pin "85") (pinfunction "CELL_RI_85") (pintype "bidirectional"))
    )
    (net (code "18") (name "CELL_RI_EXT") (class "Default")
      (node (ref "R38") (pin "2") (pinfunction "2_2") (pintype "passive"))
      (node (ref "U8") (pin "4") (pinfunction "Y_4") (pintype "bidirectional"))
    )
    (net (code "19") (name "CELL_RX") (class "Default")
      (node (ref "U1") (pin "83") (pinfunction "CELL_GPS_RX_83") (pintype "bidirectional"))
    )
    (net (code "20") (name "CELL_TX") (class "Default")
      (node (ref "U1") (pin "84") (pinfunction "CELL_GPS_TX_84") (pintype "bidirectional"))
    )
    (net (code "21") (name "CELL_VBUS") (class "Default")
      (node (ref "TP35") (pin "TP") (pinfunction "TP_TP") (pintype "input"))
      (node (ref "U1") (pin "15") (pinfunction "CELL_VBUS_15") (pintype "bidirectional"))
    )
    (net (code "22") (name "CLK1") (class "Default")
      (node (ref "TP40") (pin "TP") (pinfunction "TP_TP") (pintype "input"))
      (node (ref "U1") (pin "98") (pinfunction "CLK1_98") (pintype "bidirectional"))
    )
    (net (code "23") (name "CLKOUT") (class "Default")
      (node (ref "U10") (pin "13") (pinfunction "CLKOUT_13") (pintype "bidirectional"))
    )
    (net (code "24") (name "D_N") (class "Default")
      (node (ref "D8") (pin "2") (pinfunction "2_2") (pintype "bidirectional"))
      (node (ref "J2") (pin "A7") (pinfunction "DA-_A7") (pintype "bidirectional"))
      (node (ref "J2") (pin "B7") (pinfunction "DB-_B7") (pintype "bidirectional"))
      (node (ref "R15") (pin "1") (pinfunction "1_1") (pintype "bidirectional"))
    )
    (net (code "25") (name "D_P") (class "Default")
      (node (ref "D9") (pin "2") (pinfunction "2_2") (pintype "bidirectional"))
      (node (ref "J2") (pin "A6") (pinfunction "DA+_A6") (pintype "bidirectional"))
      (node (ref "J2") (pin "B6") (pinfunction "DB+_B6") (pintype "bidirectional"))
      (node (ref "R16") (pin "1") (pinfunction "1_1") (pintype "bidirectional"))
    )
    (net (code "26") (name "G") (class "Default")
      (node (ref "R12") (pin "1") (pinfunction "1_1") (pintype "bidirectional"))
      (node (ref "U1") (pin "29") (pinfunction "GREEN_29") (pintype "bidirectional"))
    )
    (net (code "27") (name "GND") (class "Default")
      (node (ref "BUTTON") (pin "1") (pinfunction "P$1_1") (pintype "bidirectional"))
      (node (ref "BUTTON") (pin "2") (pinfunction "P$2_2") (pintype "bidirectional"))
      (node (ref "BUTTON1") (pin "1") (pinfunction "P$1_1") (pintype "bidirectional"))
      (node (ref "BUTTON1") (pin "2") (pinfunction "P$2_2") (pintype "bidirectional"))
      (node (ref "BUTTON2") (pin "1") (pinfunction "P$1_1") (pintype "bidirectional"))
      (node (ref "BUTTON2") (pin "2") (pinfunction "P$2_2") (pintype "bidirectional"))
      (node (ref "C1") (pin "2") (pinfunction "2_2") (pintype "bidirectional"))
      (node (ref "C10") (pin "1") (pinfunction "1_1") (pintype "passive"))
      (node (ref "C11") (pin "-") (pinfunction "-_-") (pintype "passive"))
      (node (ref "C12") (pin "2") (pinfunction "2_2") (pintype "bidirectional"))
      (node (ref "C13") (pin "1") (pinfunction "1_1") (pintype "bidirectional"))
      (node (ref "C14") (pin "1") (pinfunction "1_1") (pintype "bidirectional"))
      (node (ref "C15") (pin "1") (pinfunction "1_1") (pintype "bidirectional"))
      (node (ref "C16") (pin "2") (pinfunction "2_2") (pintype "bidirectional"))
      (node (ref "C17") (pin "2") (pinfunction "2_2") (pintype "bidirectional"))
      (node (ref "C18") (pin "2") (pinfunction "2_2") (pintype "bidirectional"))
      (node (ref "C2") (pin "2") (pinfunction "2_2") (pintype "passive"))
      (node (ref "C21") (pin "2") (pinfunction "2_2") (pintype "bidirectional"))
      (node (ref "C22") (pin "2") (pinfunction "2_2") (pintype "bidirectional"))
      (node (ref "C24") (pin "2") (pinfunction "2_2") (pintype "bidirectional"))
      (node (ref "C25") (pin "1") (pinfunction "1_1") (pintype "bidirectional"))
      (node (ref "C26") (pin "1") (pinfunction "1_1") (pintype "bidirectional"))
      (node (ref "C27") (pin "2") (pinfunction "2_2") (pintype "bidirectional"))
      (node (ref "C28") (pin "2") (pinfunction "2_2") (pintype "bidirectional"))
      (node (ref "C3") (pin "1") (pinfunction "1_1") (pintype "passive"))
      (node (ref "C30") (pin "2") (pinfunction "2_2") (pintype "bidirectional"))
      (node (ref "C31") (pin "2") (pinfunction "2_2") (pintype "bidirectional"))
      (node (ref "C32") (pin "2") (pinfunction "2_2") (pintype "bidirectional"))
      (node (ref "C33") (pin "1") (pinfunction "1_1") (pintype "bidirectional"))
      (node (ref "C34") (pin "1") (pinfunction "1_1") (pintype "bidirectional"))
      (node (ref "C35") (pin "2") (pinfunction "2_2") (pintype "bidirectional"))
      (node (ref "C36") (pin "2") (pinfunction "2_2") (pintype "passive"))
      (node (ref "C37") (pin "2") (pinfunction "2_2") (pintype "passive"))
      (node (ref "C38") (pin "2") (pinfunction "2_2") (pintype "passive"))
      (node (ref "C39") (pin "2") (pinfunction "2_2") (pintype "passive"))
      (node (ref "C40") (pin "2") (pinfunction "2_2") (pintype "bidirectional"))
      (node (ref "C41") (pin "2") (pinfunction "2_2") (pintype "passive"))
      (node (ref "C42") (pin "2") (pinfunction "2_2") (pintype "passive"))
      (node (ref "C43") (pin "-") (pinfunction "-_-") (pintype "passive"))
      (node (ref "C44") (pin "1") (pinfunction "1_1") (pintype "bidirectional"))
      (node (ref "C45") (pin "1") (pinfunction "1_1") (pintype "bidirectional"))
      (node (ref "C46") (pin "2") (pinfunction "2_2") (pintype "bidirectional"))
      (node (ref "C47") (pin "2") (pinfunction "2_2") (pintype "bidirectional"))
      (node (ref "C48") (pin "2") (pinfunction "2_2") (pintype "bidirectional"))
      (node (ref "C49") (pin "2") (pinfunction "2_2") (pintype "bidirectional"))
      (node (ref "C5") (pin "2") (pinfunction "2_2") (pintype "bidirectional"))
      (node (ref "C50") (pin "2") (pinfunction "2_2") (pintype "bidirectional"))
      (node (ref "C51") (pin "2") (pinfunction "2_2") (pintype "bidirectional"))
      (node (ref "C54") (pin "2") (pinfunction "2_2") (pintype "bidirectional"))
      (node (ref "C56") (pin "2") (pinfunction "2_2") (pintype "bidirectional"))
      (node (ref "C6") (pin "2") (pinfunction "2_2") (pintype "bidirectional"))
      (node (ref "C7") (pin "2") (pinfunction "2_2") (pintype "bidirectional"))
      (node (ref "C8") (pin "2") (pinfunction "2_2") (pintype "bidirectional"))
      (node (ref "C9") (pin "2") (pinfunction "2_2") (pintype "bidirectional"))
      (node (ref "D10") (pin "2") (pinfunction "2_2") (pintype "passive"))
      (node (ref "D11") (pin "2") (pinfunction "2_2") (pintype "bidirectional"))
      (node (ref "D12") (pin "2") (pinfunction "2_2") (pintype "bidirectional"))
      (node (ref "D13") (pin "2") (pinfunction "2_2") (pintype "bidirectional"))
      (node (ref "D14") (pin "2") (pinfunction "2_2") (pintype "bidirectional"))
      (node (ref "D3") (pin "A") (pinfunction "A_A") (pintype "passive"))
      (node (ref "D6") (pin "2") (pinfunction "2_2") (pintype "passive"))
      (node (ref "D8") (pin "1") (pinfunction "1_1") (pintype "bidirectional"))
      (node (ref "D9") (pin "1") (pinfunction "1_1") (pintype "bidirectional"))
      (node (ref "DEBUG") (pin "3") (pinfunction "3_3") (pintype "bidirectional"))
      (node (ref "DEBUG") (pin "5") (pinfunction "5_5") (pintype "bidirectional"))
      (node (ref "DEBUG") (pin "9") (pinfunction "9_9") (pintype "bidirectional"))
      (node (ref "ESD1") (pin "1") (pinfunction "A1_1") (pintype "passive"))
      (node (ref "ESD2") (pin "2") (pinfunction "A2_2") (pintype "passive"))
      (node (ref "J1") (pin "8") (pinfunction "8_8") (pintype "passive"))
      (node (ref "J2") (pin "A1") (pinfunction "GNDA1_A1") (pintype "power_in"))
      (node (ref "J2") (pin "A12") (pinfunction "GNDA2_A12") (pintype "power_in"))
      (node (ref "J2") (pin "B1") (pinfunction "GNDB1_B1") (pintype "power_in"))
      (node (ref "J2") (pin "B12") (pinfunction "GNDB2_B12") (pintype "power_in"))
      (node (ref "J6") (pin "GND") (pinfunction "1_GND") (pintype "passive"))
      (node (ref "L13") (pin "2") (pinfunction "2_2") (pintype "bidirectional"))
      (node (ref "R11") (pin "1") (pinfunction "1_1") (pintype "passive"))
      (node (ref "R14") (pin "2") (pinfunction "2_2") (pintype "bidirectional"))
      (node (ref "R23") (pin "1") (pinfunction "1_1") (pintype "passive"))
      (node (ref "R24") (pin "1") (pinfunction "1_1") (pintype "bidirectional"))
      (node (ref "R26") (pin "2") (pinfunction "2_2") (pintype "bidirectional"))
      (node (ref "R27") (pin "1") (pinfunction "1_1") (pintype "bidirectional"))
      (node (ref "R29") (pin "1") (pinfunction "1_1") (pintype "bidirectional"))
      (node (ref "R30") (pin "2") (pinfunction "2_2") (pintype "passive"))
      (node (ref "R37") (pin "1") (pinfunction "1_1") (pintype "bidirectional"))
      (node (ref "R39") (pin "1") (pinfunction "1_1") (pintype "bidirectional"))
      (node (ref "R40") (pin "1") (pinfunction "1_1") (pintype "bidirectional"))
      (node (ref "R41") (pin "2") (pinfunction "2_2") (pintype "bidirectional"))
      (node (ref "R44") (pin "1") (pinfunction "1_1") (pintype "bidirectional"))
      (node (ref "R50") (pin "2") (pinfunction "2_2") (pintype "bidirectional"))
      (node (ref "R53") (pin "1") (pinfunction "1_1") (pintype "passive"))
      (node (ref "R67") (pin "1") (pinfunction "1_1") (pintype "bidirectional"))
      (node (ref "TP18") (pin "TP") (pinfunction "TP_TP") (pintype "input"))
      (node (ref "TP20") (pin "TP") (pinfunction "TP_TP") (pintype "input"))
      (node (ref "TP22") (pin "TP") (pinfunction "TP_TP") (pintype "input"))
      (node (ref "TP24") (pin "TP") (pinfunction "TP_TP") (pintype "input"))
      (node (ref "TP25") (pin "TP") (pinfunction "TP_TP") (pintype "input"))
      (node (ref "TP26") (pin "TP") (pinfunction "TP_TP") (pintype "input"))
      (node (ref "TP32") (pin "TP") (pinfunction "TP_TP") (pintype "input"))
      (node (ref "TP52") (pin "TP") (pinfunction "TP_TP") (pintype "input"))
      (node (ref "U1") (pin "1") (pinfunction "GND_1") (pintype "bidirectional"))
      (node (ref "U1") (pin "10") (pinfunction "GND_10") (pintype "bidirectional"))
      (node (ref "U1") (pin "105") (pinfunction "GND_105") (pintype "bidirectional"))
      (node (ref "U1") (pin "106") (pinfunction "GND_106") (pintype "bidirectional"))
      (node (ref "U1") (pin "107") (pinfunction "GND_107") (pintype "bidirectional"))
      (node (ref "U1") (pin "108") (pinfunction "GND_108") (pintype "bidirectional"))
      (node (ref "U1") (pin "109") (pinfunction "GND_109") (pintype "bidirectional"))
      (node (ref "U1") (pin "110") (pinfunction "GND_110") (pintype "bidirectional"))
      (node (ref "U1") (pin "25") (pinfunction "GND_25") (pintype "bidirectional"))
      (node (ref "U1") (pin "31") (pinfunction "GND_31") (pintype "bidirectional"))
      (node (ref "U1") (pin "42") (pinfunction "GND_42") (pintype "bidirectional"))
      (node (ref "U1") (pin "43") (pinfunction "GND_43") (pintype "bidirectional"))
      (node (ref "U1") (pin "48") (pinfunction "GND_48") (pintype "bidirectional"))
      (node (ref "U1") (pin "52") (pinfunction "GND_52") (pintype "bidirectional"))
      (node (ref "U1") (pin "54") (pinfunction "GND_54") (pintype "bidirectional"))
      (node (ref "U1") (pin "63") (pinfunction "AGND/GND_63") (pintype "bidirectional"))
      (node (ref "U1") (pin "67") (pinfunction "GND_67") (pintype "bidirectional"))
      (node (ref "U1") (pin "70") (pinfunction "GND_70") (pintype "bidirectional"))
      (node (ref "U1") (pin "75") (pinfunction "GND_75") (pintype "bidirectional"))
      (node (ref "U1") (pin "8") (pinfunction "GND_8") (pintype "bidirectional"))
      (node (ref "U1") (pin "86") (pinfunction "GND_86") (pintype "bidirectional"))
      (node (ref "U1") (pin "88") (pinfunction "GND_88") (pintype "bidirectional"))
      (node (ref "U1") (pin "89") (pinfunction "GND_89") (pintype "bidirectional"))
      (node (ref "U1") (pin "93") (pinfunction "GND_93") (pintype "bidirectional"))
      (node (ref "U1") (pin "95") (pinfunction "GND_95") (pintype "bidirectional"))
      (node (ref "U10") (pin "19") (pinfunction "VPRG2_19") (pintype "bidirectional"))
      (node (ref "U10") (pin "35") (pinfunction "PGND_35") (pintype "power_in"))
      (node (ref "U10") (pin "36") (pinfunction "PGND_36") (pintype "power_in"))
      (node (ref "U10") (pin "37") (pinfunction "PGND_37") (pintype "power_in"))
      (node (ref "U10") (pin "6") (pinfunction "SGND_6") (pintype "power_in"))
      (node (ref "U11") (pin "2") (pinfunction "GND_2") (pintype "bidirectional"))
      (node (ref "U12") (pin "P$2") (pinfunction "VSS_P$2") (pintype "bidirectional"))
      (node (ref "U12") (pin "P$5") (pinfunction "VSS_P$5") (pintype "bidirectional"))
      (node (ref "U2") (pin "1") (pinfunction "N_1") (pintype "power_in"))
      (node (ref "U4") (pin "13") (pinfunction "/EN_13") (pintype "bidirectional"))
      (node (ref "U4") (pin "6") (pinfunction "GND_6") (pintype "bidirectional"))
      (node (ref "U5") (pin "P$2") (pinfunction "VSS_P$2") (pintype "bidirectional"))
      (node (ref "U5") (pin "P$5") (pinfunction "VSS_P$5") (pintype "bidirectional"))
      (node (ref "U6") (pin "1") (pinfunction "GND_1") (pintype "power_in"))
      (node (ref "U6") (pin "4") (pinfunction "GND_4") (pintype "power_in"))
      (node (ref "U7") (pin "2") (pinfunction "GND_2") (pintype "power_in"))
      (node (ref "U7") (pin "3") (pinfunction "GND_3") (pintype "power_in"))
      (node (ref "U7") (pin "5") (pinfunction "GND_5") (pintype "power_in"))
      (node (ref "U8") (pin "3") (pinfunction "GND_3") (pintype "power_in"))
      (node (ref "U9") (pin "4") (pinfunction "VSS_4") (pintype "power_in"))
    )
    (net (code "28") (name "GNSS_ANT_PWR") (class "Default")
      (node (ref "D1") (pin "1") (pinfunction "P$1_1") (pintype "bidirectional"))
      (node (ref "L8") (pin "1") (pinfunction "1_1") (pintype "bidirectional"))
      (node (ref "U1") (pin "91") (pinfunction "GNSS_ANT_PWR_91") (pintype "bidirectional"))
    )
    (net (code "29") (name "GNSS_BAT") (class "Default")
      (node (ref "C11") (pin "+") (pinfunction "+_+") (pintype "passive"))
      (node (ref "R20") (pin "1") (pinfunction "1_1") (pintype "passive"))
      (node (ref "TP9") (pin "TP") (pinfunction "TP_TP") (pintype "input"))
      (node (ref "U1") (pin "2") (pinfunction "GNSS_BAT_2") (pintype "bidirectional"))
    )
    (net (code "30") (name "GNSS_BOOT") (class "Default")
      (node (ref "TP6") (pin "TP") (pinfunction "TP_TP") (pintype "input"))
      (node (ref "U1") (pin "90") (pinfunction "GNSS_BOOT_90") (pintype "bidirectional"))
    )
    (net (code "31") (name "GNSS_LNA_EN") (class "Default")
      (node (ref "U1") (pin "92") (pinfunction "GNSS_LNA_EN_92") (pintype "bidirectional"))
      (node (ref "U6") (pin "6") (pinfunction "PON_6") (pintype "input"))
    )
    (net (code "32") (name "GNSS_N") (class "Default")
      (node (ref "S1") (pin "A3") (pinfunction "A3_A3") (pintype "passive"))
      (node (ref "TP14") (pin "TP") (pinfunction "TP_TP") (pintype "input"))
      (node (ref "TP34") (pin "TP") (pinfunction "TP_TP") (pintype "input"))
      (node (ref "U1") (pin "6") (pinfunction "GNSS_N_6") (pintype "bidirectional"))
    )
    (net (code "33") (name "GNSS_P") (class "Default")
      (node (ref "S1") (pin "A2") (pinfunction "A2_A2") (pintype "passive"))
      (node (ref "TP19") (pin "TP") (pinfunction "TP_TP") (pintype "input"))
      (node (ref "TP5") (pin "TP") (pinfunction "TP_TP") (pintype "input"))
      (node (ref "U1") (pin "5") (pinfunction "GNSS_P_5") (pintype "bidirectional"))
    )
    (net (code "34") (name "GNSS_RESET") (class "Default")
      (node (ref "TP8") (pin "TP") (pinfunction "TP_TP") (pintype "input"))
      (node (ref "U1") (pin "3") (pinfunction "GNSS_RESET_3") (pintype "bidirectional"))
    )
    (net (code "35") (name "GNSS_RF") (class "Default")
      (node (ref "C20") (pin "1") (pinfunction "1_1") (pintype "bidirectional"))
      (node (ref "U1") (pin "94") (pinfunction "GNSS_RF_94") (pintype "bidirectional"))
    )
    (net (code "36") (name "GNSS_TIME_PULSE") (class "Default")
      (node (ref "TP7") (pin "TP") (pinfunction "TP_TP") (pintype "input"))
      (node (ref "U1") (pin "7") (pinfunction "GNSS_PULSE_7") (pintype "bidirectional"))
    )
    (net (code "37") (name "GNSS_VBUS") (class "Default")
      (node (ref "C44") (pin "2") (pinfunction "2_2") (pintype "bidirectional"))
      (node (ref "TP30") (pin "TP") (pinfunction "TP_TP") (pintype "input"))
      (node (ref "U1") (pin "4") (pinfunction "GNSS_VBUS_4") (pintype "bidirectional"))
      (node (ref "U12") (pin "P$1") (pinfunction "VOUT_P$1") (pintype "bidirectional"))
    )
    (net (code "38") (name "GPIO1") (class "Default")
      (node (ref "R36") (pin "2") (pinfunction "2_2") (pintype "bidirectional"))
      (node (ref "U4") (pin "8") (pinfunction "NO3_8") (pintype "bidirectional"))
    )
    (net (code "39") (name "GPIO1_O") (class "Default")
      (node (ref "D14") (pin "1") (pinfunction "1_1") (pintype "bidirectional"))
      (node (ref "J1") (pin "7") (pinfunction "7_7") (pintype "passive"))
      (node (ref "TP51") (pin "TP") (pinfunction "TP_TP") (pintype "input"))
      (node (ref "U4") (pin "7") (pinfunction "COM3_7") (pintype "bidirectional"))
    )
    (net (code "40") (name "GPS_ANT_IN") (class "Default")
      (node (ref "C19") (pin "2") (pinfunction "2_2") (pintype "bidirectional"))
      (node (ref "C25") (pin "2") (pinfunction "2_2") (pintype "bidirectional"))
      (node (ref "D12") (pin "1") (pinfunction "1_1") (pintype "bidirectional"))
      (node (ref "U3") (pin "P$1") (pinfunction "SIGNAL_P$1") (pintype "bidirectional"))
    )
    (net (code "41") (name "IMON") (class "Default")
      (node (ref "U10") (pin "17") (pinfunction "IMON_17") (pintype "bidirectional"))
    )
    (net (code "42") (name "INTVCC") (class "Default")
      (node (ref "C9") (pin "1") (pinfunction "1_1") (pintype "bidirectional"))
      (node (ref "R18") (pin "1") (pinfunction "1_1") (pintype "bidirectional"))
      (node (ref "R19") (pin "2") (pinfunction "2_2") (pintype "bidirectional"))
      (node (ref "R25") (pin "1") (pinfunction "1_1") (pintype "bidirectional"))
      (node (ref "R28") (pin "1") (pinfunction "1_1") (pintype "bidirectional"))
      (node (ref "U10") (pin "21") (pinfunction "INTVCC_21") (pintype "bidirectional"))
    )
    (net (code "43") (name "LI+") (class "Default")
      (node (ref "J6") (pin "VCC") (pinfunction "2_VCC") (pintype "passive"))
      (node (ref "U$1") (pin "P$1") (pinfunction "TP_P$1") (pintype "bidirectional"))
      (node (ref "U1") (pin "53") (pinfunction "LI+_53") (pintype "bidirectional"))
    )
    (net (code "44") (name "MCU1_N") (class "Default")
      (node (ref "S1") (pin "A5") (pinfunction "A5_A5") (pintype "passive"))
      (node (ref "U1") (pin "68") (pinfunction "MCU_D-_68") (pintype "bidirectional"))
    )
    (net (code "45") (name "MCU1_P") (class "Default")
      (node (ref "S1") (pin "A4") (pinfunction "A4_A4") (pintype "passive"))
      (node (ref "U1") (pin "69") (pinfunction "MCU_D+_69") (pintype "bidirectional"))
    )
    (net (code "46") (name "MCU_N") (class "Default")
      (node (ref "R15") (pin "2") (pinfunction "2_2") (pintype "bidirectional"))
      (node (ref "S1") (pin "3") (pinfunction "3_3") (pintype "passive"))
      (node (ref "S1") (pin "5") (pinfunction "5_5") (pintype "passive"))
    )
    (net (code "47") (name "MCU_P") (class "Default")
      (node (ref "R16") (pin "2") (pinfunction "2_2") (pintype "bidirectional"))
      (node (ref "S1") (pin "2") (pinfunction "2_2") (pintype "passive"))
      (node (ref "S1") (pin "4") (pinfunction "4_4") (pintype "passive"))
    )
    (net (code "48") (name "MCU_RX") (class "Default")
      (node (ref "U1") (pin "71") (pinfunction "MCU_RX_71") (pintype "bidirectional"))
      (node (ref "U4") (pin "4") (pinfunction "NO2_4") (pintype "bidirectional"))
    )
    (net (code "49") (name "MCU_RX_O") (class "Default")
      (node (ref "D13") (pin "1") (pinfunction "1_1") (pintype "bidirectional"))
      (node (ref "J1") (pin "6") (pinfunction "6_6") (pintype "passive"))
      (node (ref "TP50") (pin "TP") (pinfunction "TP_TP") (pintype "input"))
      (node (ref "U4") (pin "5") (pinfunction "COM2_5") (pintype "bidirectional"))
    )
    (net (code "50") (name "MCU_TX") (class "Default")
      (node (ref "U1") (pin "72") (pinfunction "MUC_TX_72") (pintype "bidirectional"))
      (node (ref "U4") (pin "1") (pinfunction "NO1_1") (pintype "bidirectional"))
    )
    (net (code "51") (name "MCU_TX_O") (class "Default")
      (node (ref "D11") (pin "1") (pinfunction "1_1") (pintype "bidirectional"))
      (node (ref "J1") (pin "5") (pinfunction "5_5") (pintype "passive"))
      (node (ref "TP49") (pin "TP") (pinfunction "TP_TP") (pintype "input"))
      (node (ref "U4") (pin "2") (pinfunction "COM1_2") (pintype "bidirectional"))
    )
    (net (code "52") (name "MISO0") (class "Default")
      (node (ref "U1") (pin "40") (pinfunction "A5_40") (pintype "bidirectional"))
      (node (ref "U9") (pin "2") (pinfunction "SO_2") (pintype "output"))
    )
    (net (code "53") (name "MISO1") (class "Default")
      (node (ref "TP39") (pin "TP") (pinfunction "TP_TP") (pintype "input"))
      (node (ref "U1") (pin "97") (pinfunction "MISO1_97") (pintype "bidirectional"))
    )
    (net (code "54") (name "MODE") (class "Default")
      (node (ref "BUTTON") (pin "3") (pinfunction "P$3_3") (pintype "bidirectional"))
      (node (ref "BUTTON") (pin "4") (pinfunction "P$4_4") (pintype "bidirectional"))
      (node (ref "R43") (pin "2") (pinfunction "2_2") (pintype "bidirectional"))
      (node (ref "U1") (pin "32") (pinfunction "MODE_32") (pintype "bidirectional"))
    )
    (net (code "55") (name "MOSI0") (class "Default")
      (node (ref "U1") (pin "41") (pinfunction "A4_41") (pintype "bidirectional"))
      (node (ref "U9") (pin "5") (pinfunction "SI_5") (pintype "output"))
    )
    (net (code "56") (name "MOSI1") (class "Default")
      (node (ref "TP37") (pin "TP") (pinfunction "TP_TP") (pintype "input"))
      (node (ref "U1") (pin "96") (pinfunction "MOSI1_96") (pintype "bidirectional"))
    )
    (net (code "57") (name "N$11") (class "Default")
      (node (ref "R3") (pin "2") (pinfunction "2_2") (pintype "passive"))
      (node (ref "R5") (pin "1") (pinfunction "1_1") (pintype "passive"))
      (node (ref "R53") (pin "2") (pinfunction "2_2") (pintype "passive"))
      (node (ref "U2") (pin "2") (pinfunction "P_2") (pintype "power_in"))
    )
    (net (code "58") (name "NFC1") (class "Default")
      (node (ref "C34") (pin "2") (pinfunction "2_2") (pintype "bidirectional"))
      (node (ref "C52") (pin "2") (pinfunction "2_2") (pintype "bidirectional"))
      (node (ref "C53") (pin "2") (pinfunction "2_2") (pintype "bidirectional"))
      (node (ref "NFC1") (pin "2@1") (pinfunction "GND_2@1") (pintype "passive"))
      (node (ref "NFC1") (pin "2@2") (pinfunction "GND_2@2") (pintype "passive"))
      (node (ref "R26") (pin "1") (pinfunction "1_1") (pintype "bidirectional"))
      (node (ref "R51") (pin "1") (pinfunction "1_1") (pintype "bidirectional"))
      (node (ref "U$10") (pin "TP") (pinfunction "TP_TP") (pintype "input"))
    )
    (net (code "59") (name "NFC1_1") (class "Default")
      (node (ref "R51") (pin "2") (pinfunction "2_2") (pintype "bidirectional"))
      (node (ref "U1") (pin "27") (pinfunction "NFC1_27") (pintype "bidirectional"))
    )
    (net (code "60") (name "NFC2") (class "Default")
      (node (ref "C33") (pin "2") (pinfunction "2_2") (pintype "bidirectional"))
      (node (ref "C52") (pin "1") (pinfunction "1_1") (pintype "bidirectional"))
      (node (ref "C53") (pin "1") (pinfunction "1_1") (pintype "bidirectional"))
      (node (ref "NFC1") (pin "1") (pinfunction "1_1") (pintype "passive"))
      (node (ref "R27") (pin "2") (pinfunction "2_2") (pintype "bidirectional"))
      (node (ref "R52") (pin "1") (pinfunction "1_1") (pintype "bidirectional"))
      (node (ref "U$9") (pin "TP") (pinfunction "TP_TP") (pintype "input"))
    )
    (net (code "61") (name "NFC2_2") (class "Default")
      (node (ref "R52") (pin "2") (pinfunction "2_2") (pintype "bidirectional"))
      (node (ref "U1") (pin "26") (pinfunction "NFC2_26") (pintype "bidirectional"))
    )
    (net (code "62") (name "Net-(BUTTON2-P$3)") (class "Default")
      (node (ref "BUTTON2") (pin "3") (pinfunction "P$3_3") (pintype "bidirectional"))
      (node (ref "BUTTON2") (pin "4") (pinfunction "P$4_4") (pintype "bidirectional"))
      (node (ref "R9") (pin "2") (pinfunction "2_2") (pintype "bidirectional"))
    )
    (net (code "63") (name "Net-(C4-Pad1)") (class "Default")
      (node (ref "C4") (pin "1") (pinfunction "1_1") (pintype "bidirectional"))
      (node (ref "L1") (pin "1") (pinfunction "1_1") (pintype "bidirectional"))
      (node (ref "U10") (pin "24") (pinfunction "SW_24") (pintype "power_in"))
      (node (ref "U10") (pin "25") (pinfunction "SW_25") (pintype "power_in"))
      (node (ref "U10") (pin "26") (pinfunction "SW_26") (pintype "power_in"))
    )
    (net (code "64") (name "Net-(C10-Pad2)") (class "Default")
      (node (ref "C10") (pin "2") (pinfunction "2_2") (pintype "passive"))
      (node (ref "R1") (pin "1") (pinfunction "1_1") (pintype "passive"))
      (node (ref "R10") (pin "2") (pinfunction "2_2") (pintype "passive"))
    )
    (net (code "65") (name "Net-(C23-Pad2)") (class "Default")
      (node (ref "C23") (pin "2") (pinfunction "2_2") (pintype "bidirectional"))
      (node (ref "C29") (pin "1") (pinfunction "1_1") (pintype "bidirectional"))
    )
    (net (code "66") (name "Net-(C31-Pad1)") (class "Default")
      (node (ref "C31") (pin "1") (pinfunction "1_1") (pintype "bidirectional"))
      (node (ref "C37") (pin "1") (pinfunction "1_1") (pintype "passive"))
      (node (ref "C40") (pin "1") (pinfunction "1_1") (pintype "bidirectional"))
      (node (ref "C41") (pin "1") (pinfunction "1_1") (pintype "passive"))
      (node (ref "C43") (pin "+") (pinfunction "+_+") (pintype "passive"))
      (node (ref "C46") (pin "1") (pinfunction "1_1") (pintype "bidirectional"))
      (node (ref "L7") (pin "2") (pinfunction "2_2") (pintype "passive"))
      (node (ref "R17") (pin "2") (pinfunction "2_2") (pintype "bidirectional"))
      (node (ref "U10") (pin "30") (pinfunction "VIN_30") (pintype "power_in"))
      (node (ref "U10") (pin "31") (pinfunction "VIN_31") (pintype "power_in"))
      (node (ref "U10") (pin "32") (pinfunction "VIN_32") (pintype "power_in"))
    )
    (net (code "67") (name "Net-(C39-Pad1)") (class "Default")
      (node (ref "C39") (pin "1") (pinfunction "1_1") (pintype "passive"))
      (node (ref "C42") (pin "1") (pinfunction "1_1") (pintype "passive"))
      (node (ref "L6") (pin "2") (pinfunction "2_2") (pintype "passive"))
      (node (ref "L7") (pin "1") (pinfunction "1_1") (pintype "passive"))
    )
    (net (code "68") (name "Net-(D1-P$2)") (class "Default")
      (node (ref "D1") (pin "2") (pinfunction "P$2_2") (pintype "bidirectional"))
      (node (ref "R20") (pin "2") (pinfunction "2_2") (pintype "passive"))
    )
    (net (code "69") (name "Net-(D2-P$1)") (class "Default")
      (node (ref "D2") (pin "1") (pinfunction "P$1_1") (pintype "bidirectional"))
      (node (ref "R33") (pin "1") (pinfunction "1_1") (pintype "bidirectional"))
    )
    (net (code "70") (name "Net-(D2-P$2)") (class "Default")
      (node (ref "D2") (pin "2") (pinfunction "P$2_2") (pintype "bidirectional"))
      (node (ref "DEBUG") (pin "1") (pinfunction "1_1") (pintype "bidirectional"))
    )
    (net (code "71") (name "Net-(D4-P$2)") (class "Default")
      (node (ref "D4") (pin "2") (pinfunction "P$2_2") (pintype "bidirectional"))
      (node (ref "R5") (pin "2") (pinfunction "2_2") (pintype "passive"))
    )
    (net (code "72") (name "Net-(LED1-A)") (class "Default")
      (node (ref "LED1") (pin "2") (pinfunction "A_2") (pintype "bidirectional"))
      (node (ref "R6") (pin "2") (pinfunction "2_2") (pintype "bidirectional"))
    )
    (net (code "73") (name "Net-(LED3-Pad2)") (class "Default")
      (node (ref "LED3") (pin "2") (pinfunction "2_2") (pintype "passive"))
      (node (ref "R46") (pin "2") (pinfunction "2_2") (pintype "bidirectional"))
    )
    (net (code "74") (name "Net-(LED3-Pad3)") (class "Default")
      (node (ref "LED3") (pin "3") (pinfunction "3_3") (pintype "passive"))
      (node (ref "R13") (pin "2") (pinfunction "2_2") (pintype "bidirectional"))
    )
    (net (code "75") (name "Net-(LED3-Pad4)") (class "Default")
      (node (ref "LED3") (pin "4") (pinfunction "4_4") (pintype "passive"))
      (node (ref "R12") (pin "2") (pinfunction "2_2") (pintype "bidirectional"))
    )
    (net (code "76") (name "Net-(LED4-A)") (class "Default")
      (node (ref "LED4") (pin "2") (pinfunction "A_2") (pintype "bidirectional"))
      (node (ref "R8") (pin "2") (pinfunction "2_2") (pintype "bidirectional"))
    )
    (net (code "77") (name "Net-(R41-Pad1)") (class "Default")
      (node (ref "R41") (pin "1") (pinfunction "1_1") (pintype "bidirectional"))
      (node (ref "R42") (pin "1") (pinfunction "1_1") (pintype "bidirectional"))
      (node (ref "R45") (pin "2") (pinfunction "2_2") (pintype "bidirectional"))
    )
    (net (code "78") (name "Net-(U4-IN)") (class "Default")
      (node (ref "R35") (pin "2") (pinfunction "2_2") (pintype "bidirectional"))
      (node (ref "R39") (pin "2") (pinfunction "2_2") (pintype "bidirectional"))
      (node (ref "U4") (pin "15") (pinfunction "IN_15") (pintype "bidirectional"))
    )
    (net (code "79") (name "Net-(U6-AI)") (class "Default")
      (node (ref "L4") (pin "1") (pinfunction "1_1") (pintype "bidirectional"))
      (node (ref "U6") (pin "5") (pinfunction "AI_5") (pintype "input"))
    )
    (net (code "80") (name "Net-(U6-VCC)") (class "Default")
      (node (ref "C12") (pin "1") (pinfunction "1_1") (pintype "bidirectional"))
      (node (ref "C18") (pin "1") (pinfunction "1_1") (pintype "bidirectional"))
      (node (ref "L8") (pin "2") (pinfunction "2_2") (pintype "bidirectional"))
      (node (ref "U6") (pin "2") (pinfunction "VCC_2") (pintype "power_in"))
    )
    (net (code "81") (name "Net-(U7-OUTPUT)") (class "Default")
      (node (ref "L4") (pin "2") (pinfunction "2_2") (pintype "bidirectional"))
      (node (ref "U7") (pin "4") (pinfunction "OUTPUT_4") (pintype "bidirectional"))
    )
    (net (code "82") (name "Net-(U8-A)") (class "Default")
      (node (ref "R4") (pin "1") (pinfunction "1_1") (pintype "passive"))
      (node (ref "U8") (pin "2") (pinfunction "A_2") (pintype "bidirectional"))
    )
    (net (code "83") (name "Net-(U9-~{WP})") (class "Default")
      (node (ref "R21") (pin "1") (pinfunction "1_1") (pintype "bidirectional"))
      (node (ref "U9") (pin "3") (pinfunction "~{WP}_3") (pintype "input"))
    )
    (net (code "84") (name "Net-(U10-BOOST)") (class "Default")
      (node (ref "C4") (pin "2") (pinfunction "2_2") (pintype "bidirectional"))
      (node (ref "U10") (pin "27") (pinfunction "BOOST_27") (pintype "bidirectional"))
    )
    (net (code "85") (name "Net-(U10-EXTVCC)") (class "Default")
      (node (ref "C36") (pin "1") (pinfunction "1_1") (pintype "passive"))
      (node (ref "C47") (pin "1") (pinfunction "1_1") (pintype "bidirectional"))
      (node (ref "L1") (pin "2") (pinfunction "2_2") (pintype "bidirectional"))
      (node (ref "L5") (pin "1") (pinfunction "1_1") (pintype "passive"))
      (node (ref "U10") (pin "10") (pinfunction "VFB_10") (pintype "bidirectional"))
      (node (ref "U10") (pin "20") (pinfunction "EXTVCC_20") (pintype "bidirectional"))
    )
    (net (code "86") (name "Net-(U10-FREQ)") (class "Default")
      (node (ref "R23") (pin "2") (pinfunction "2_2") (pintype "passive"))
      (node (ref "U10") (pin "11") (pinfunction "FREQ_11") (pintype "bidirectional"))
    )
    (net (code "87") (name "Net-(U10-ITH)") (class "Default")
      (node (ref "R25") (pin "2") (pinfunction "2_2") (pintype "bidirectional"))
      (node (ref "U10") (pin "9") (pinfunction "ITH_9") (pintype "bidirectional"))
    )
    (net (code "88") (name "Net-(U10-PLLIN{slash}MODE)") (class "Default")
      (node (ref "R28") (pin "2") (pinfunction "2_2") (pintype "bidirectional"))
      (node (ref "R29") (pin "2") (pinfunction "2_2") (pintype "bidirectional"))
      (node (ref "U10") (pin "12") (pinfunction "PLLIN/MODE_12") (pintype "bidirectional"))
    )
    (net (code "89") (name "Net-(U10-RUN)") (class "Default")
      (node (ref "R17") (pin "1") (pinfunction "1_1") (pintype "bidirectional"))
      (node (ref "U10") (pin "3") (pinfunction "RUN_3") (pintype "bidirectional"))
    )
    (net (code "90") (name "Net-(U11-EN)") (class "Default")
      (node (ref "C49") (pin "1") (pinfunction "1_1") (pintype "bidirectional"))
      (node (ref "R22") (pin "1") (pinfunction "1_1") (pintype "passive"))
      (node (ref "R31") (pin "2") (pinfunction "2_2") (pintype "passive"))
      (node (ref "U11") (pin "3") (pinfunction "EN_3") (pintype "bidirectional"))
    )
    (net (code "91") (name "Net-(U11-ILIM)") (class "Default")
      (node (ref "R11") (pin "2") (pinfunction "2_2") (pintype "passive"))
      (node (ref "U11") (pin "5") (pinfunction "ILIM_5") (pintype "bidirectional"))
    )
    (net (code "92") (name "Net-(U11-~{FAULT})") (class "Default")
      (node (ref "R31") (pin "1") (pinfunction "1_1") (pintype "passive"))
      (node (ref "U11") (pin "4") (pinfunction "~{FAULT}_4") (pintype "bidirectional"))
    )
    (net (code "93") (name "PGOOD") (class "Default")
      (node (ref "R18") (pin "2") (pinfunction "2_2") (pintype "bidirectional"))
      (node (ref "U10") (pin "14") (pinfunction "PGOOD_14") (pintype "bidirectional"))
    )
    (net (code "94") (name "PMID") (class "Default")
      (node (ref "U1") (pin "47") (pinfunction "PMID_47") (pintype "bidirectional"))
    )
    (net (code "95") (name "R") (class "Default")
      (node (ref "R13") (pin "1") (pinfunction "1_1") (pintype "bidirectional"))
      (node (ref "U1") (pin "30") (pinfunction "RED_30") (pintype "bidirectional"))
    )
    (net (code "96") (name "RESET") (class "Default")
      (node (ref "BUTTON1") (pin "3") (pinfunction "P$3_3") (pintype "bidirectional"))
      (node (ref "BUTTON1") (pin "4") (pinfunction "P$4_4") (pintype "bidirectional"))
      (node (ref "DEBUG") (pin "10") (pinfunction "10_10") (pintype "bidirectional"))
      (node (ref "TP11") (pin "TP") (pinfunction "TP_TP") (pintype "input"))
      (node (ref "U1") (pin "33") (pinfunction "RESET_33") (pintype "bidirectional"))
    )
    (net (code "97") (name "RIND") (class "Default")
      (node (ref "R24") (pin "2") (pinfunction "2_2") (pintype "bidirectional"))
      (node (ref "U10") (pin "8") (pinfunction "RIND_8") (pintype "bidirectional"))
    )
    (net (code "98") (name "RTC_BAT") (class "Default")
      (node (ref "C1") (pin "1") (pinfunction "1_1") (pintype "bidirectional"))
      (node (ref "R3") (pin "1") (pinfunction "1_1") (pintype "passive"))
      (node (ref "U1") (pin "73") (pinfunction "RTC_BAT_73") (pintype "bidirectional"))
    )
    (net (code "99") (name "RTC_BTN") (class "Default")
      (node (ref "R2") (pin "1") (pinfunction "1_1") (pintype "bidirectional"))
      (node (ref "U1") (pin "74") (pinfunction "RTC_BTN_74") (pintype "bidirectional"))
    )
    (net (code "100") (name "SAW_IN") (class "Default")
      (node (ref "C19") (pin "1") (pinfunction "1_1") (pintype "bidirectional"))
      (node (ref "C22") (pin "1") (pinfunction "1_1") (pintype "bidirectional"))
      (node (ref "U7") (pin "1") (pinfunction "INPUT_1") (pintype "input"))
    )
    (net (code "101") (name "SCK0") (class "Default")
      (node (ref "U1") (pin "39") (pinfunction "A6_39") (pintype "bidirectional"))
      (node (ref "U9") (pin "6") (pinfunction "SCK_6") (pintype "input"))
    )
    (net (code "102") (name "SHIELD") (class "Default")
      (node (ref "C17") (pin "1") (pinfunction "1_1") (pintype "bidirectional"))
      (node (ref "J2") (pin "S1") (pinfunction "SHIELD_S1") (pintype "passive"))
      (node (ref "J2") (pin "S2") (pinfunction "SHIELD_S2") (pintype "passive"))
      (node (ref "J2") (pin "S3") (pinfunction "SHIELD_S3") (pintype "passive"))
      (node (ref "J2") (pin "S4") (pinfunction "SHIELD_S4") (pintype "passive"))
      (node (ref "L13") (pin "1") (pinfunction "1_1") (pintype "bidirectional"))
      (node (ref "R14") (pin "1") (pinfunction "1_1") (pintype "bidirectional"))
    )
    (net (code "103") (name "SIM_CLK") (class "Default")
      (node (ref "C14") (pin "2") (pinfunction "2_2") (pintype "bidirectional"))
      (node (ref "TP29") (pin "TP") (pinfunction "TP_TP") (pintype "input"))
      (node (ref "U1") (pin "104") (pinfunction "SIM_CLK_104") (pintype "bidirectional"))
    )
    (net (code "104") (name "SIM_DATA") (class "Default")
      (node (ref "C15") (pin "2") (pinfunction "2_2") (pintype "bidirectional"))
      (node (ref "R7") (pin "1") (pinfunction "1_1") (pintype "bidirectional"))
      (node (ref "TP31") (pin "TP") (pinfunction "TP_TP") (pintype "input"))
      (node (ref "U1") (pin "103") (pinfunction "SIM_DATA_103") (pintype "bidirectional"))
    )
    (net (code "105") (name "SIM_RST") (class "Default")
      (node (ref "C13") (pin "2") (pinfunction "2_2") (pintype "bidirectional"))
      (node (ref "TP28") (pin "TP") (pinfunction "TP_TP") (pintype "input"))
      (node (ref "U1") (pin "102") (pinfunction "SIM_RST_102") (pintype "bidirectional"))
    )
    (net (code "106") (name "SIM_VCC") (class "Default")
      (node (ref "C16") (pin "1") (pinfunction "1_1") (pintype "bidirectional"))
      (node (ref "R7") (pin "2") (pinfunction "2_2") (pintype "bidirectional"))
      (node (ref "TP27") (pin "TP") (pinfunction "TP_TP") (pintype "input"))
      (node (ref "U1") (pin "101") (pinfunction "SIM_VCC_101") (pintype "bidirectional"))
    )
    (net (code "107") (name "SOM9") (class "Default")
      (node (ref "U1") (pin "9") (pinfunction "NC_9") (pintype "bidirectional"))
    )
    (net (code "108") (name "SOM18") (class "Default")
      (node (ref "U1") (pin "18") (pinfunction "NC_18") (pintype "bidirectional"))
    )
    (net (code "109") (name "SOM19") (class "Default")
      (node (ref "U1") (pin "19") (pinfunction "NC_19") (pintype "bidirectional"))
    )
    (net (code "110") (name "SOM20") (class "Default")
      (node (ref "U1") (pin "20") (pinfunction "NC_20") (pintype "bidirectional"))
    )
    (net (code "111") (name "SOM21") (class "Default")
      (node (ref "U1") (pin "21") (pinfunction "NC_21") (pintype "bidirectional"))
    )
    (net (code "112") (name "SOM34") (class "Default")
      (node (ref "U1") (pin "34") (pinfunction "NC_34") (pintype "bidirectional"))
    )
    (net (code "113") (name "SOM35") (class "Default")
      (node (ref "U1") (pin "35") (pinfunction "NC_35") (pintype "bidirectional"))
    )
    (net (code "114") (name "SOM36") (class "Default")
      (node (ref "U1") (pin "36") (pinfunction "NC_36") (pintype "bidirectional"))
    )
    (net (code "115") (name "SOM37") (class "Default")
      (node (ref "U1") (pin "37") (pinfunction "NC_37") (pintype "bidirectional"))
    )
    (net (code "116") (name "SOM44") (class "Default")
      (node (ref "U1") (pin "44") (pinfunction "NC_44") (pintype "bidirectional"))
    )
    (net (code "117") (name "SOM59") (class "Default")
      (node (ref "U1") (pin "59") (pinfunction "NC_59") (pintype "bidirectional"))
    )
    (net (code "118") (name "SOM60") (class "Default")
      (node (ref "U1") (pin "60") (pinfunction "NC_60") (pintype "bidirectional"))
    )
    (net (code "119") (name "SOM61") (class "Default")
      (node (ref "U1") (pin "61") (pinfunction "NC_61") (pintype "bidirectional"))
    )
    (net (code "120") (name "SOM62") (class "Default")
      (node (ref "U1") (pin "62") (pinfunction "NC_62") (pintype "bidirectional"))
    )
    (net (code "121") (name "SOM76") (class "Default")
      (node (ref "U1") (pin "76") (pinfunction "NC_76") (pintype "bidirectional"))
    )
    (net (code "122") (name "SOM77") (class "Default")
      (node (ref "U1") (pin "77") (pinfunction "NC_77") (pintype "bidirectional"))
    )
    (net (code "123") (name "SOM78") (class "Default")
      (node (ref "U1") (pin "78") (pinfunction "NC_78") (pintype "bidirectional"))
    )
    (net (code "124") (name "SOM79") (class "Default")
      (node (ref "U1") (pin "79") (pinfunction "NC_79") (pintype "bidirectional"))
    )
    (net (code "125") (name "SOM80") (class "Default")
      (node (ref "U1") (pin "80") (pinfunction "NC_80") (pintype "bidirectional"))
    )
    (net (code "126") (name "SOM81") (class "Default")
      (node (ref "U1") (pin "81") (pinfunction "NC_81") (pintype "bidirectional"))
    )
    (net (code "127") (name "SOM82") (class "Default")
      (node (ref "U1") (pin "82") (pinfunction "NC_82") (pintype "bidirectional"))
    )
    (net (code "128") (name "SS") (class "Default")
      (node (ref "C35") (pin "1") (pinfunction "1_1") (pintype "bidirectional"))
      (node (ref "R19") (pin "1") (pinfunction "1_1") (pintype "bidirectional"))
      (node (ref "U10") (pin "15") (pinfunction "SS_15") (pintype "bidirectional"))
    )
    (net (code "129") (name "STAT") (class "Default")
      (node (ref "LED1") (pin "1") (pinfunction "K_1") (pintype "bidirectional"))
      (node (ref "U1") (pin "50") (pinfunction "STAT_50") (pintype "bidirectional"))
    )
    (net (code "130") (name "SWDCLK") (class "Default")
      (node (ref "DEBUG") (pin "4") (pinfunction "4_4") (pintype "bidirectional"))
      (node (ref "TP13") (pin "TP") (pinfunction "TP_TP") (pintype "input"))
      (node (ref "U1") (pin "23") (pinfunction "SWDCLK_23") (pintype "bidirectional"))
    )
    (net (code "131") (name "SWDIO") (class "Default")
      (node (ref "DEBUG") (pin "2") (pinfunction "2_2") (pintype "bidirectional"))
      (node (ref "TP15") (pin "TP") (pinfunction "TP_TP") (pintype "input"))
      (node (ref "U1") (pin "22") (pinfunction "SWDIO_22") (pintype "bidirectional"))
    )
    (net (code "132") (name "SWO") (class "Default")
      (node (ref "DEBUG") (pin "6") (pinfunction "6_6") (pintype "bidirectional"))
      (node (ref "TP12") (pin "TP") (pinfunction "TP_TP") (pintype "input"))
      (node (ref "U1") (pin "24") (pinfunction "SWO_24") (pintype "bidirectional"))
    )
    (net (code "133") (name "TS") (class "Default")
      (node (ref "R50") (pin "1") (pinfunction "1_1") (pintype "bidirectional"))
      (node (ref "U1") (pin "46") (pinfunction "TS_46") (pintype "bidirectional"))
    )
    (net (code "134") (name "UVBUS") (class "Default")
      (node (ref "C45") (pin "2") (pinfunction "2_2") (pintype "bidirectional"))
      (node (ref "R67") (pin "2") (pinfunction "2_2") (pintype "bidirectional"))
      (node (ref "S1") (pin "A1") (pinfunction "A1_A1") (pintype "passive"))
      (node (ref "TP17") (pin "TP") (pinfunction "TP_TP") (pintype "input"))
      (node (ref "TP33") (pin "TP") (pinfunction "TP_TP") (pintype "input"))
      (node (ref "U12") (pin "P$3") (pinfunction "CE_P$3") (pintype "bidirectional"))
      (node (ref "U12") (pin "P$4") (pinfunction "VIN_P$4") (pintype "bidirectional"))
    )
    (net (code "135") (name "VBUS_SOM") (class "Default")
      (node (ref "C21") (pin "1") (pinfunction "1_1") (pintype "bidirectional"))
      (node (ref "C26") (pin "2") (pinfunction "2_2") (pintype "bidirectional"))
      (node (ref "C7") (pin "1") (pinfunction "1_1") (pintype "bidirectional"))
      (node (ref "F1") (pin "2") (pinfunction "2_2") (pintype "bidirectional"))
      (node (ref "S1") (pin "1") (pinfunction "1_1") (pintype "passive"))
      (node (ref "U1") (pin "51") (pinfunction "VBUS_51") (pintype "bidirectional"))
    )
    (net (code "136") (name "VCC") (class "Default")
      (node (ref "C54") (pin "1") (pinfunction "1_1") (pintype "bidirectional"))
      (node (ref "R35") (pin "1") (pinfunction "1_1") (pintype "bidirectional"))
      (node (ref "R40") (pin "2") (pinfunction "2_2") (pintype "bidirectional"))
      (node (ref "R47") (pin "2") (pinfunction "2_2") (pintype "bidirectional"))
      (node (ref "TP44") (pin "TP") (pinfunction "TP_TP") (pintype "input"))
      (node (ref "U4") (pin "14") (pinfunction "VDD_14") (pintype "bidirectional"))
      (node (ref "U5") (pin "P$1") (pinfunction "VOUT_P$1") (pintype "bidirectional"))
    )
    (net (code "137") (name "VIN") (class "Default")
      (node (ref "C50") (pin "1") (pinfunction "1_1") (pintype "bidirectional"))
      (node (ref "D5") (pin "A") (pinfunction "A_A") (pintype "passive"))
      (node (ref "J1") (pin "1") (pinfunction "1_1") (pintype "passive"))
      (node (ref "TP23") (pin "TP") (pinfunction "TP_TP") (pintype "input"))
      (node (ref "TP43") (pin "TP") (pinfunction "TP_TP") (pintype "input"))
      (node (ref "TP45") (pin "TP") (pinfunction "TP_TP") (pintype "input"))
    )
    (net (code "138") (name "VIN1") (class "Default")
      (node (ref "C38") (pin "1") (pinfunction "1_1") (pintype "passive"))
      (node (ref "D3") (pin "C") (pinfunction "C_C") (pintype "passive"))
      (node (ref "D5") (pin "C") (pinfunction "C_C") (pintype "passive"))
      (node (ref "L6") (pin "1") (pinfunction "1_1") (pintype "passive"))
      (node (ref "R30") (pin "1") (pinfunction "1_1") (pintype "passive"))
    )
    (net (code "139") (name "VIN_SOM") (class "Default")
      (node (ref "C30") (pin "1") (pinfunction "1_1") (pintype "bidirectional"))
      (node (ref "C32") (pin "1") (pinfunction "1_1") (pintype "bidirectional"))
      (node (ref "C6") (pin "1") (pinfunction "1_1") (pintype "bidirectional"))
      (node (ref "C8") (pin "1") (pinfunction "1_1") (pintype "bidirectional"))
      (node (ref "L5") (pin "2") (pinfunction "2_2") (pintype "passive"))
      (node (ref "TP10") (pin "TP") (pinfunction "TP_TP") (pintype "input"))
      (node (ref "U1") (pin "49") (pinfunction "VIN_49") (pintype "bidirectional"))
    )
    (net (code "140") (name "VVBUS") (class "Default")
      (node (ref "D10") (pin "1") (pinfunction "1_1") (pintype "passive"))
      (node (ref "F1") (pin "1") (pinfunction "1_1") (pintype "bidirectional"))
      (node (ref "J2") (pin "A4") (pinfunction "VBUSA1_A4") (pintype "power_in"))
      (node (ref "J2") (pin "A9") (pinfunction "VBUSA2_A9") (pintype "power_in"))
      (node (ref "J2") (pin "B4") (pinfunction "VBUSB1_B4") (pintype "power_in"))
      (node (ref "J2") (pin "B9") (pinfunction "VBUSB2_B9") (pintype "power_in"))
    )
    (net (code "141") (name "WIFI_BOOT") (class "Default")
      (node (ref "TP3") (pin "TP") (pinfunction "TP_TP") (pintype "input"))
      (node (ref "U1") (pin "12") (pinfunction "WIFI_BOOT_12") (pintype "bidirectional"))
    )
    (net (code "142") (name "WIFI_EN") (class "Default")
      (node (ref "TP4") (pin "TP") (pinfunction "TP_TP") (pintype "input"))
      (node (ref "U1") (pin "11") (pinfunction "WIFI_EN_11") (pintype "bidirectional"))
    )
    (net (code "143") (name "WIFI_RXD") (class "Default")
      (node (ref "TP1") (pin "TP") (pinfunction "TP_TP") (pintype "input"))
      (node (ref "U1") (pin "14") (pinfunction "WIFI_RXD_14") (pintype "bidirectional"))
    )
    (net (code "144") (name "WIFI_TXD") (class "Default")
      (node (ref "TP2") (pin "TP") (pinfunction "TP_TP") (pintype "input"))
      (node (ref "U1") (pin "13") (pinfunction "WIFI_TXD_13") (pintype "bidirectional"))
    )
    (net (code "145") (name "Y1") (class "Default")
      (node (ref "TP42") (pin "TP") (pinfunction "TP_TP") (pintype "input"))
      (node (ref "U1") (pin "100") (pinfunction "Y1_100") (pintype "bidirectional"))
    )
    (net (code "146") (name "Y5") (class "Default")
      (node (ref "TP41") (pin "TP") (pinfunction "TP_TP") (pintype "input"))
      (node (ref "U1") (pin "99") (pinfunction "Y5_99") (pintype "bidirectional"))
    )
    (net (code "147") (name "unconnected-(DEBUG-Pad7)") (class "Default")
      (node (ref "DEBUG") (pin "7") (pinfunction "7_7") (pintype "bidirectional"))
    )
    (net (code "148") (name "unconnected-(DEBUG-Pad8)") (class "Default")
      (node (ref "DEBUG") (pin "8") (pinfunction "8_8") (pintype "bidirectional"))
    )
    (net (code "149") (name "unconnected-(ESD1-C-Pad3)") (class "Default")
      (node (ref "ESD1") (pin "3") (pinfunction "C_3") (pintype "passive"))
    )
    (net (code "150") (name "unconnected-(ESD2-C-Pad3)") (class "Default")
      (node (ref "ESD2") (pin "3") (pinfunction "C_3") (pintype "passive"))
    )
    (net (code "151") (name "unconnected-(J2-RX1+-PadB11)") (class "Default")
      (node (ref "J2") (pin "B11") (pinfunction "RX1+_B11") (pintype "bidirectional"))
    )
    (net (code "152") (name "unconnected-(J2-RX1--PadB10)") (class "Default")
      (node (ref "J2") (pin "B10") (pinfunction "RX1-_B10") (pintype "bidirectional"))
    )
    (net (code "153") (name "unconnected-(J2-RX2+-PadA11)") (class "Default")
      (node (ref "J2") (pin "A11") (pinfunction "RX2+_A11") (pintype "bidirectional"))
    )
    (net (code "154") (name "unconnected-(J2-RX2--PadA10)") (class "Default")
      (node (ref "J2") (pin "A10") (pinfunction "RX2-_A10") (pintype "bidirectional"))
    )
    (net (code "155") (name "unconnected-(J2-SBU1-PadA8)") (class "Default")
      (node (ref "J2") (pin "A8") (pinfunction "SBU1_A8") (pintype "bidirectional"))
    )
    (net (code "156") (name "unconnected-(J2-SBU2-PadB8)") (class "Default")
      (node (ref "J2") (pin "B8") (pinfunction "SBU2_B8") (pintype "bidirectional"))
    )
    (net (code "157") (name "unconnected-(J2-TX1+-PadA2)") (class "Default")
      (node (ref "J2") (pin "A2") (pinfunction "TX1+_A2") (pintype "bidirectional"))
    )
    (net (code "158") (name "unconnected-(J2-TX1--PadA3)") (class "Default")
      (node (ref "J2") (pin "A3") (pinfunction "TX1-_A3") (pintype "bidirectional"))
    )
    (net (code "159") (name "unconnected-(J2-TX2+-PadB2)") (class "Default")
      (node (ref "J2") (pin "B2") (pinfunction "TX2+_B2") (pintype "bidirectional"))
    )
    (net (code "160") (name "unconnected-(J2-TX2--PadB3)") (class "Default")
      (node (ref "J2") (pin "B3") (pinfunction "TX2-_B3") (pintype "bidirectional"))
    )
    (net (code "161") (name "unconnected-(U4-COM4-Pad10)") (class "Default")
      (node (ref "U4") (pin "10") (pinfunction "COM4_10") (pintype "bidirectional"))
    )
    (net (code "162") (name "unconnected-(U4-NC1-Pad16)") (class "Default")
      (node (ref "U4") (pin "16") (pinfunction "NC1_16") (pintype "bidirectional"))
    )
    (net (code "163") (name "unconnected-(U4-NC2-Pad3)") (class "Default")
      (node (ref "U4") (pin "3") (pinfunction "NC2_3") (pintype "bidirectional"))
    )
    (net (code "164") (name "unconnected-(U4-NC3-Pad9)") (class "Default")
      (node (ref "U4") (pin "9") (pinfunction "NC3_9") (pintype "bidirectional"))
    )
    (net (code "165") (name "unconnected-(U4-NC4-Pad12)") (class "Default")
      (node (ref "U4") (pin "12") (pinfunction "NC4_12") (pintype "bidirectional"))
    )
    (net (code "166") (name "unconnected-(U4-NO4-Pad11)") (class "Default")
      (node (ref "U4") (pin "11") (pinfunction "NO4_11") (pintype "bidirectional"))
    )
    (net (code "167") (name "unconnected-(U10-ICTRL-Pad16)") (class "Default")
      (node (ref "U10") (pin "16") (pinfunction "ICTRL_16") (pintype "bidirectional"))
    )
    (net (code "168") (name "unconnected-(U10-OVLO-Pad7)") (class "Default")
      (node (ref "U10") (pin "7") (pinfunction "OVLO_7") (pintype "bidirectional"))
    )
    (net (code "169") (name "unconnected-(U10-VPRG1-Pad18)") (class "Default")
      (node (ref "U10") (pin "18") (pinfunction "VPRG1_18") (pintype "bidirectional"))
    )
    (net (code "170") (name "{slash}FRAM_CS") (class "Default")
      (node (ref "R32") (pin "1") (pinfunction "1_1") (pintype "bidirectional"))
      (node (ref "U1") (pin "38") (pinfunction "A7_38") (pintype "bidirectional"))
      (node (ref "U9") (pin "1") (pinfunction "~{CS}_1") (pintype "output"))
    )
    (net (code "171") (name "~{FRAM_HOLD}") (class "Default")
      (node (ref "R34") (pin "1") (pinfunction "1_1") (pintype "bidirectional"))
      (node (ref "U9") (pin "7") (pinfunction "~{HOLD}_7") (pintype "output"))
    )
  )
)
